# 1-Schematic_iCESDuck-ShieldControler.net
KiCad netlist of a schematic drawn in EasyEDA
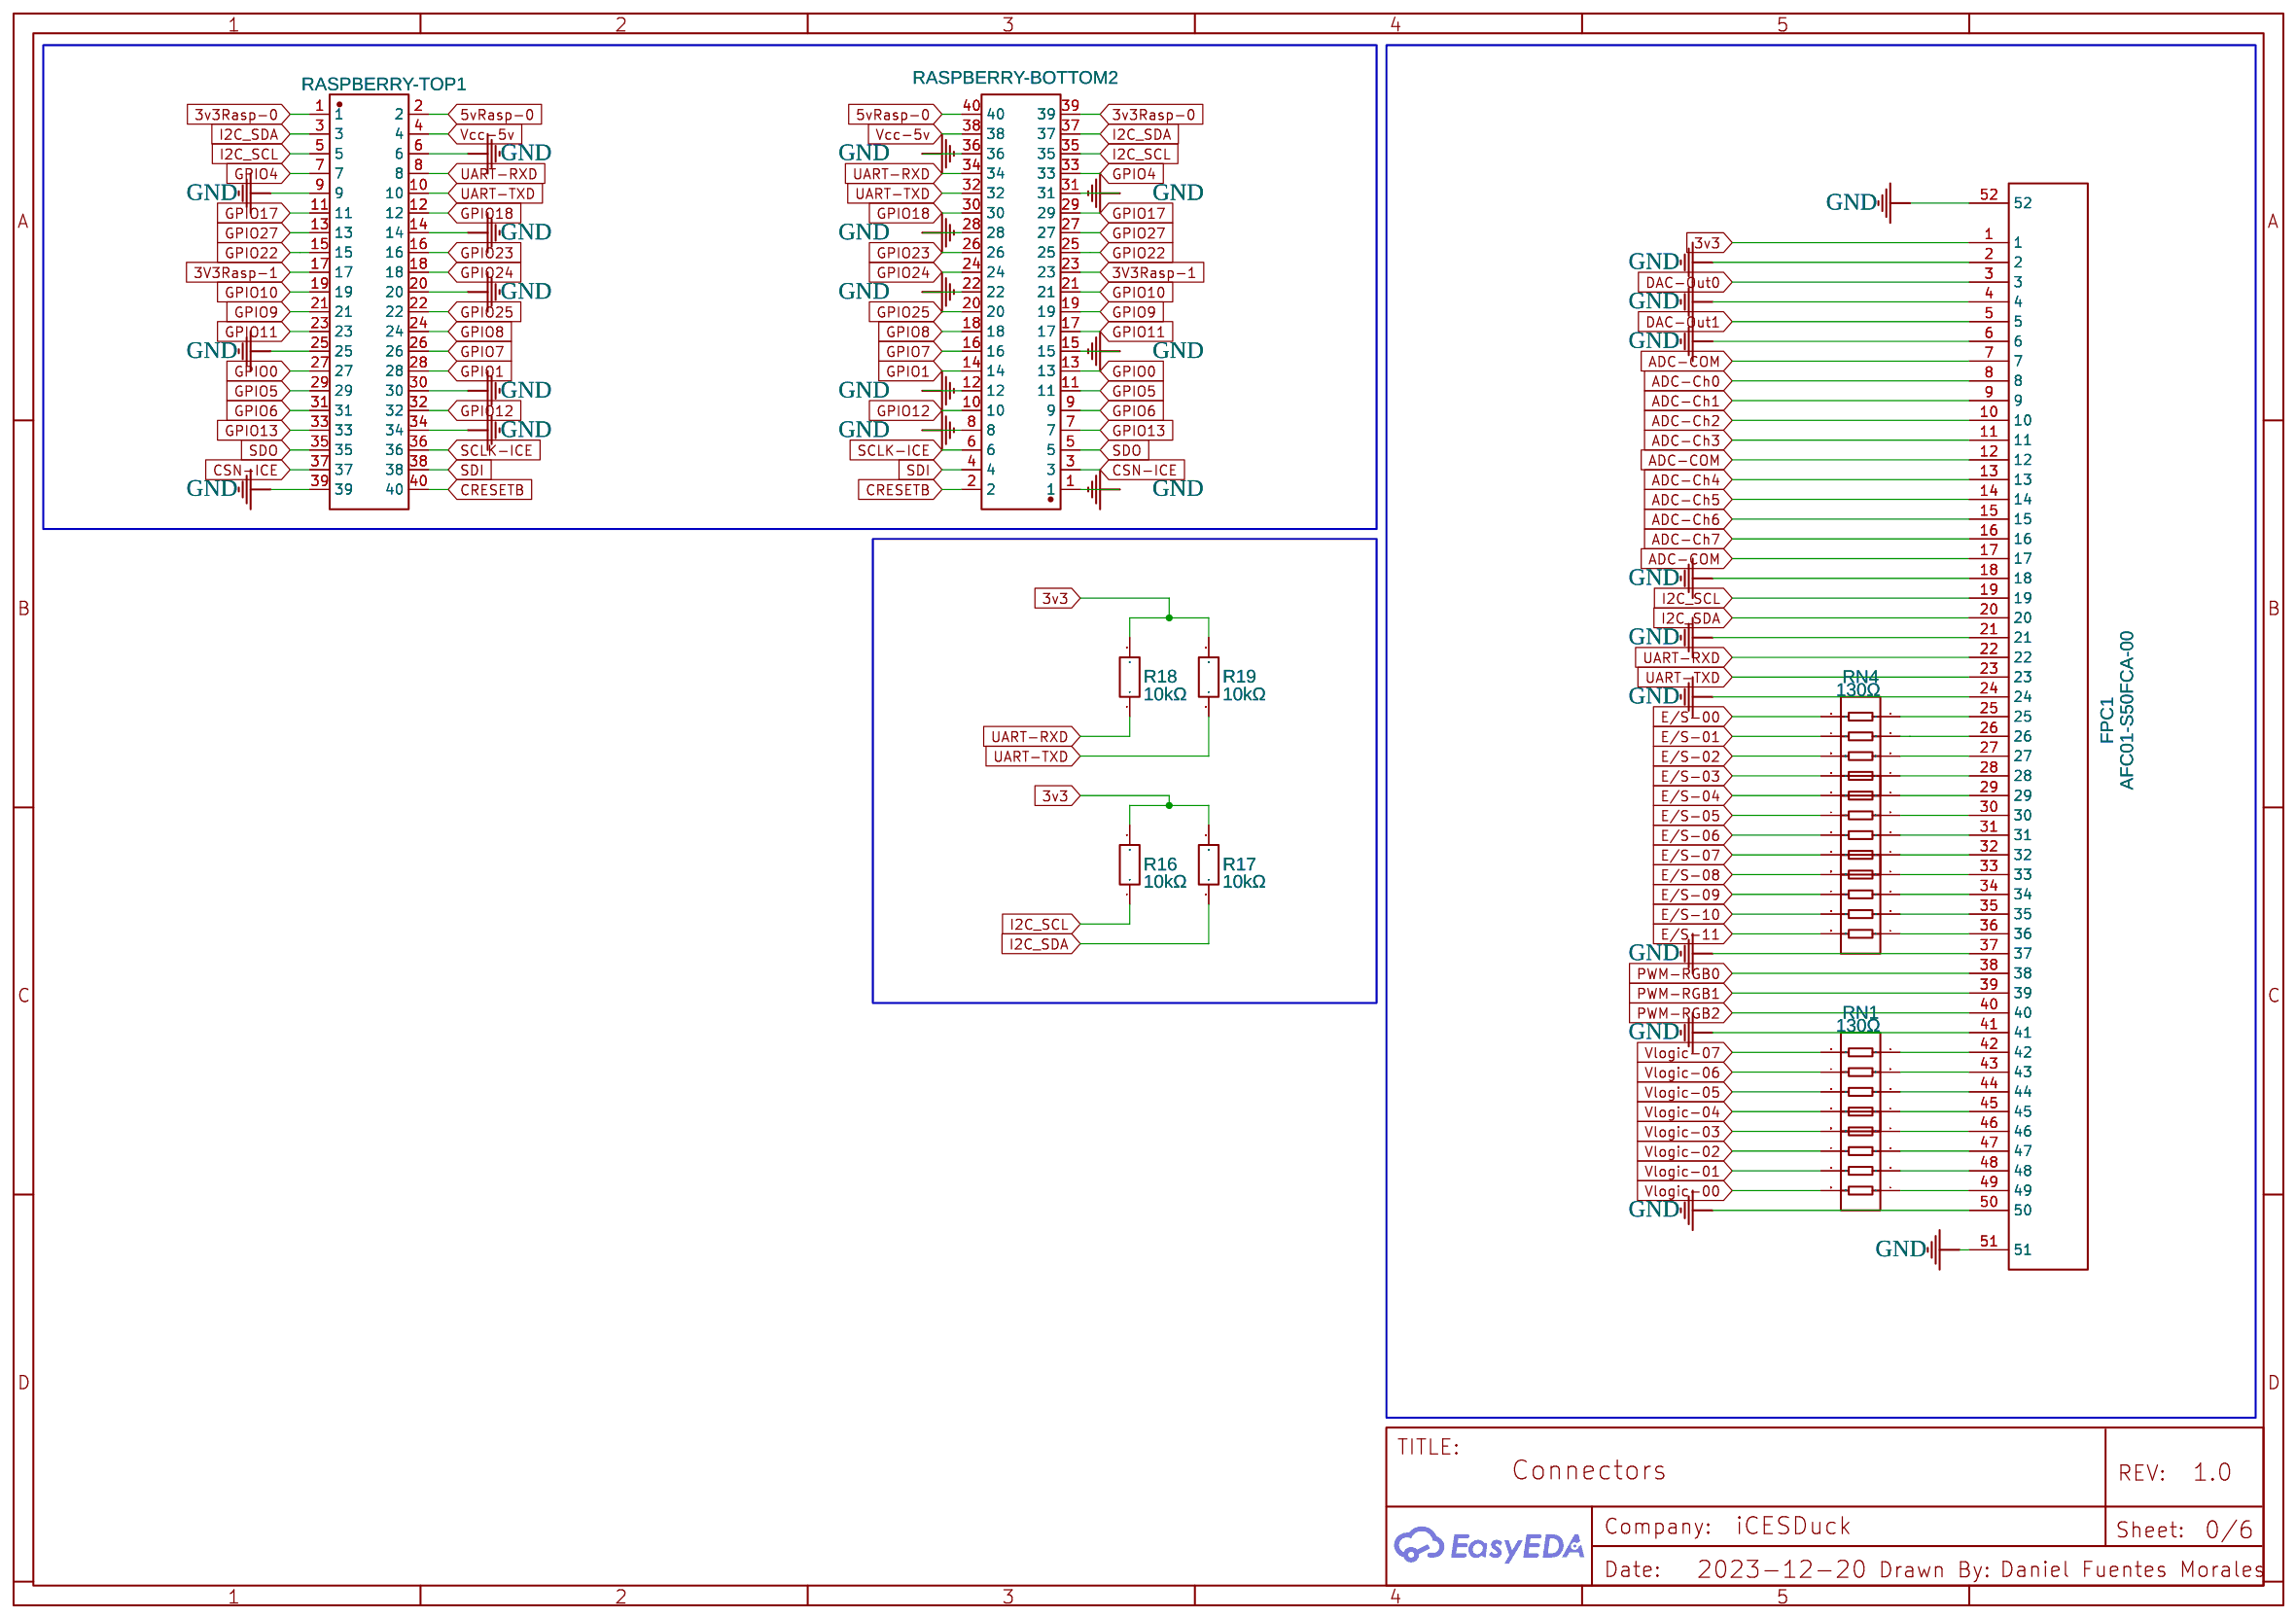
[diagram p0: Connectors]
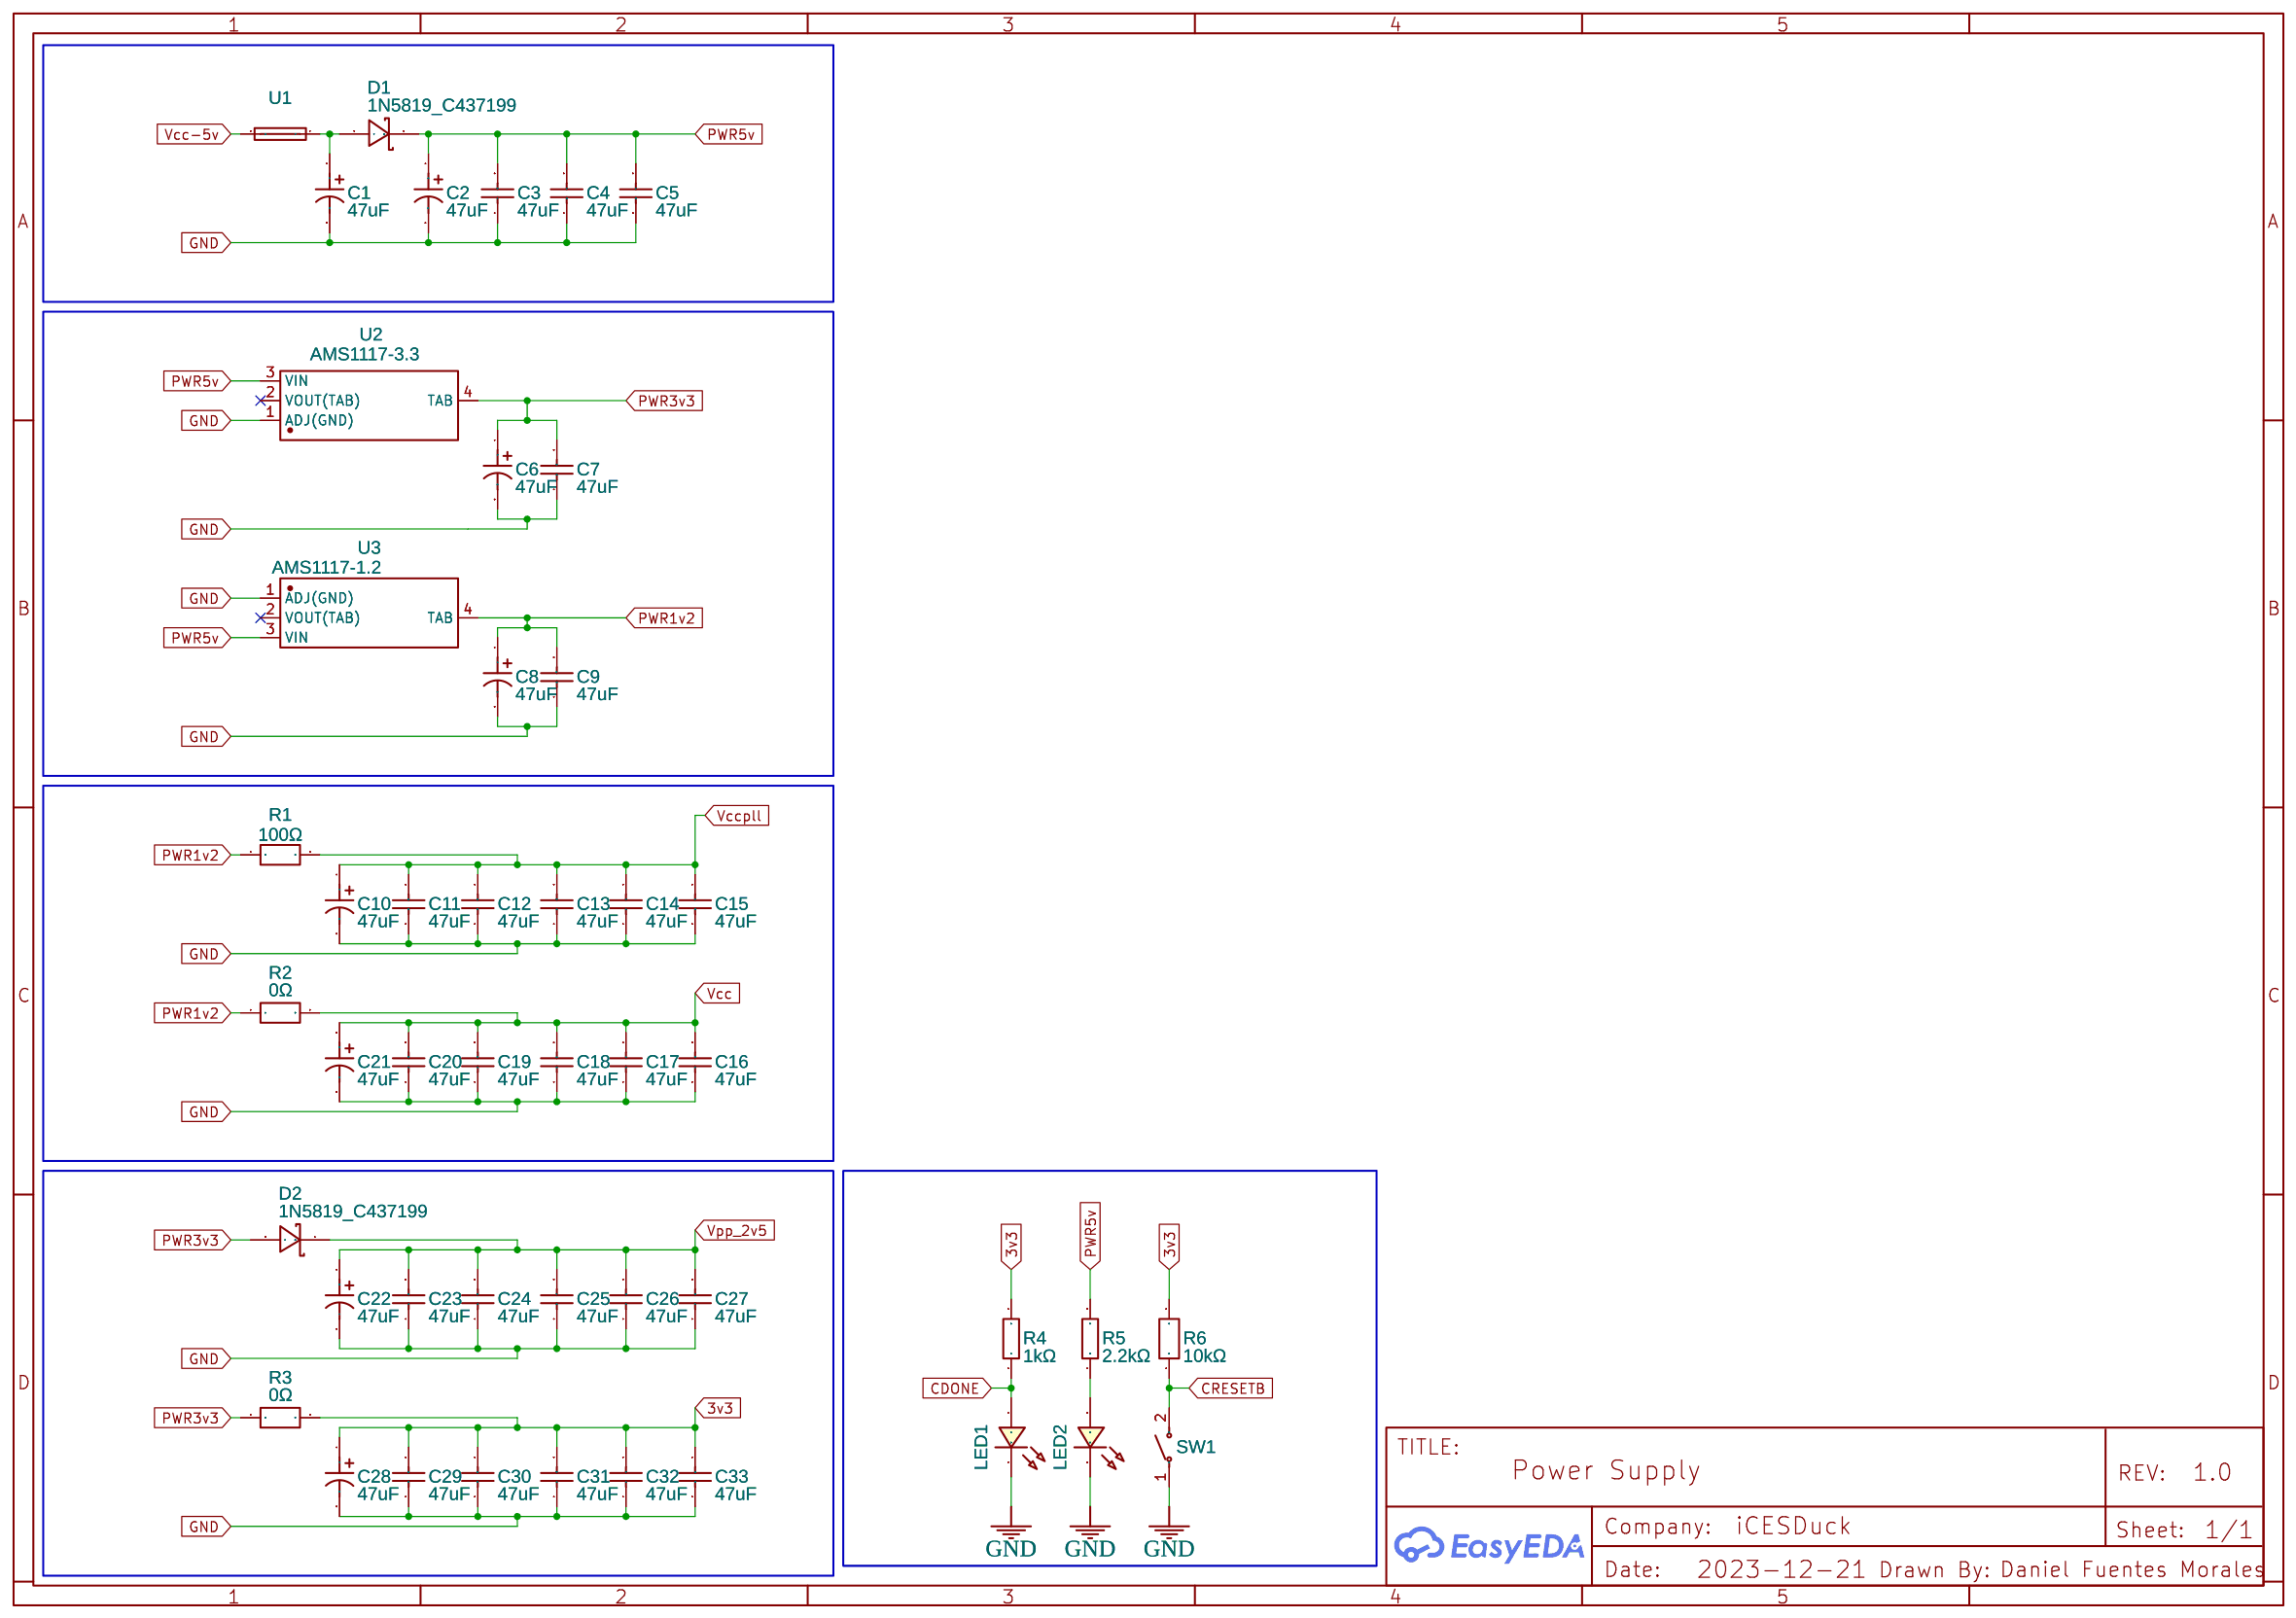
[diagram p1: power supply]
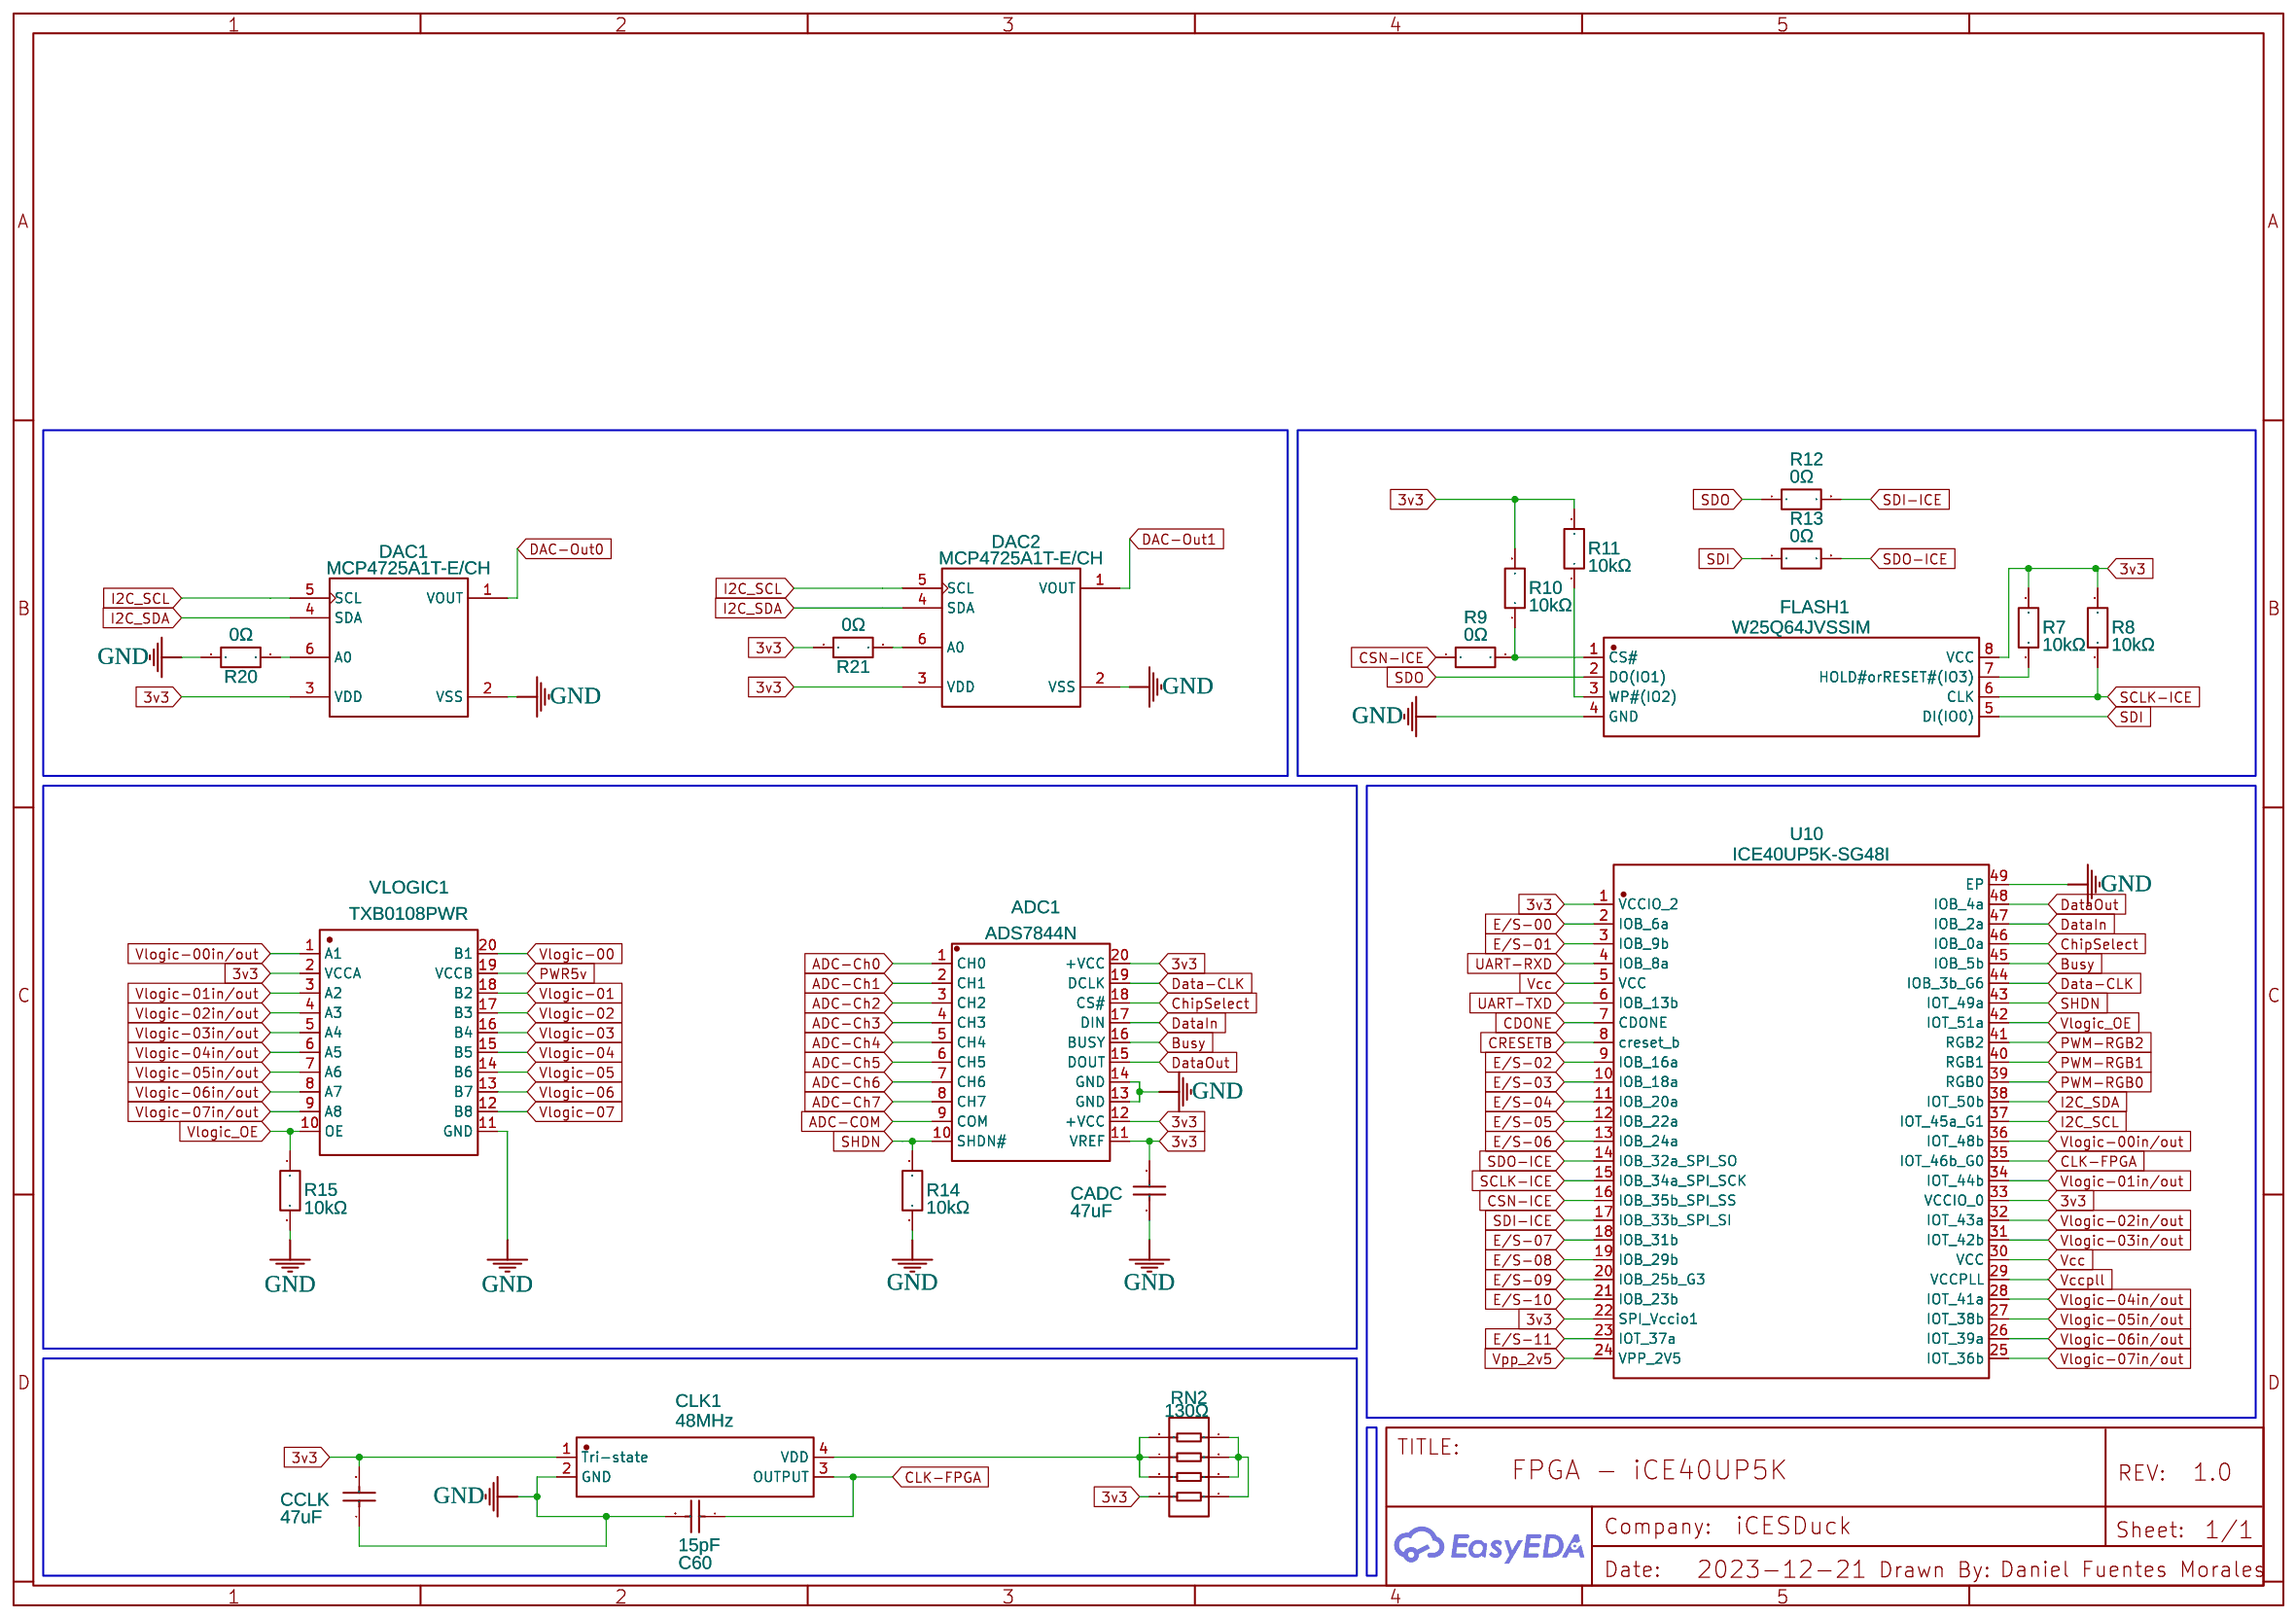
[diagram p2: FPGA - iCE40UP5k]

(export (version "E")
  (design (tool "Eeschema 10.0.6"))
  (components
    (comp (ref "FPC1")
      (value "AFC01-S50FCA-00")
      (fields (field (name "Manufacturer") "JS(钜硕电子)"))
      (libsource (lib "") (part "AFC01-S50FCA-00"))
    )
    (comp (ref "R16")
      (value "10kΩ")
      (fields (field (name "Manufacturer Part") "FRP1206J103 TS") (field (name "Manufacturer") "FOJAN(富捷)"))
      (libsource (lib "") (part "FRP1206J103 TS"))
    )
    (comp (ref "R17")
      (value "10kΩ")
      (fields (field (name "Manufacturer Part") "FRP1206J103 TS") (field (name "Manufacturer") "FOJAN(富捷)"))
      (libsource (lib "") (part "FRP1206J103 TS"))
    )
    (comp (ref "R18")
      (value "10kΩ")
      (fields (field (name "Manufacturer Part") "FRP1206J103 TS") (field (name "Manufacturer") "FOJAN(富捷)"))
      (libsource (lib "") (part "FRP1206J103 TS"))
    )
    (comp (ref "R19")
      (value "10kΩ")
      (fields (field (name "Manufacturer Part") "FRP1206J103 TS") (field (name "Manufacturer") "FOJAN(富捷)"))
      (libsource (lib "") (part "FRP1206J103 TS"))
    )
    (comp (ref "RASPBERRY-BOTTOM2")
      (value "FH-00148")
      (fields (field (name "Manufacturer") "Liansheng(连盛)"))
      (libsource (lib "") (part "FH-00148_1"))
    )
    (comp (ref "RASPBERRY-TOP1")
      (value "FH-00148")
      (fields (field (name "Manufacturer") "Liansheng(连盛)"))
      (libsource (lib "") (part "FH-00148"))
    )
    (comp (ref "RN1")
      (value "130Ω")
      (fields
        (field (name "Manufacturer Part") "4D03WGJ0131T5E")
        (field (name "Manufacturer") "UNI-ROYAL(厚声)")
      )
      (libsource (lib "") (part "4D03WGJ0131T5E"))
    )
    (comp (ref "RN3")
      (value "130Ω")
      (fields
        (field (name "Manufacturer Part") "4D03WGJ0131T5E")
        (field (name "Manufacturer") "UNI-ROYAL(厚声)")
      )
      (libsource (lib "") (part "4D03WGJ0131T5E"))
    )
    (comp (ref "RN4")
      (value "130Ω")
      (fields
        (field (name "Manufacturer Part") "4D03WGJ0131T5E")
        (field (name "Manufacturer") "UNI-ROYAL(厚声)")
      )
      (libsource (lib "") (part "4D03WGJ0131T5E"))
    )
    (comp (ref "RN5")
      (value "130Ω")
      (fields
        (field (name "Manufacturer Part") "4D03WGJ0131T5E")
        (field (name "Manufacturer") "UNI-ROYAL(厚声)")
      )
      (libsource (lib "") (part "4D03WGJ0131T5E"))
    )
    (comp (ref "RN6")
      (value "130Ω")
      (fields
        (field (name "Manufacturer Part") "4D03WGJ0131T5E")
        (field (name "Manufacturer") "UNI-ROYAL(厚声)")
      )
      (libsource (lib "") (part "4D03WGJ0131T5E"))
    )
    (comp (ref "C1")
      (value "47uF")
      (fields
        (field (name "Manufacturer Part") "CA45-A-10V-47uF-M")
        (field (name "Manufacturer") "CEC(振华新云)")
      )
      (libsource (lib "") (part "CA45-A-10V-47UF-M"))
    )
    (comp (ref "C2")
      (value "47uF")
      (fields
        (field (name "Manufacturer Part") "CA45-A-10V-47uF-M")
        (field (name "Manufacturer") "CEC(振华新云)")
      )
      (libsource (lib "") (part "CA45-A-10V-47UF-M"))
    )
    (comp (ref "C3")
      (value "47uF")
      (fields (field (name "Manufacturer Part") "C2012X5R1A476MTJ00E") (field (name "Manufacturer") "TDK"))
      (libsource (lib "") (part "C2012X5R1A476MTJ00E"))
    )
    (comp (ref "C4")
      (value "47uF")
      (fields (field (name "Manufacturer Part") "C2012X5R1A476MTJ00E") (field (name "Manufacturer") "TDK"))
      (libsource (lib "") (part "C2012X5R1A476MTJ00E"))
    )
    (comp (ref "C5")
      (value "47uF")
      (fields (field (name "Manufacturer Part") "C2012X5R1A476MTJ00E") (field (name "Manufacturer") "TDK"))
      (libsource (lib "") (part "C2012X5R1A476MTJ00E"))
    )
    (comp (ref "C6")
      (value "47uF")
      (fields
        (field (name "Manufacturer Part") "CA45-A-10V-47uF-M")
        (field (name "Manufacturer") "CEC(振华新云)")
      )
      (libsource (lib "") (part "CA45-A-10V-47UF-M"))
    )
    (comp (ref "C7")
      (value "47uF")
      (fields (field (name "Manufacturer Part") "C2012X5R1A476MTJ00E") (field (name "Manufacturer") "TDK"))
      (libsource (lib "") (part "C2012X5R1A476MTJ00E"))
    )
    (comp (ref "C8")
      (value "47uF")
      (fields
        (field (name "Manufacturer Part") "CA45-A-10V-47uF-M")
        (field (name "Manufacturer") "CEC(振华新云)")
      )
      (libsource (lib "") (part "CA45-A-10V-47UF-M"))
    )
    (comp (ref "C9")
      (value "47uF")
      (fields (field (name "Manufacturer Part") "C2012X5R1A476MTJ00E") (field (name "Manufacturer") "TDK"))
      (libsource (lib "") (part "C2012X5R1A476MTJ00E"))
    )
    (comp (ref "C10")
      (value "47uF")
      (fields
        (field (name "Manufacturer Part") "CA45-A-10V-47uF-M")
        (field (name "Manufacturer") "CEC(振华新云)")
      )
      (libsource (lib "") (part "CA45-A-10V-47UF-M"))
    )
    (comp (ref "C11")
      (value "47uF")
      (fields (field (name "Manufacturer Part") "C2012X5R1A476MTJ00E") (field (name "Manufacturer") "TDK"))
      (libsource (lib "") (part "C2012X5R1A476MTJ00E"))
    )
    (comp (ref "C12")
      (value "47uF")
      (fields (field (name "Manufacturer Part") "C2012X5R1A476MTJ00E") (field (name "Manufacturer") "TDK"))
      (libsource (lib "") (part "C2012X5R1A476MTJ00E"))
    )
    (comp (ref "C13")
      (value "47uF")
      (fields (field (name "Manufacturer Part") "C2012X5R1A476MTJ00E") (field (name "Manufacturer") "TDK"))
      (libsource (lib "") (part "C2012X5R1A476MTJ00E"))
    )
    (comp (ref "C14")
      (value "47uF")
      (fields (field (name "Manufacturer Part") "C2012X5R1A476MTJ00E") (field (name "Manufacturer") "TDK"))
      (libsource (lib "") (part "C2012X5R1A476MTJ00E"))
    )
    (comp (ref "C15")
      (value "47uF")
      (fields (field (name "Manufacturer Part") "C2012X5R1A476MTJ00E") (field (name "Manufacturer") "TDK"))
      (libsource (lib "") (part "C2012X5R1A476MTJ00E"))
    )
    (comp (ref "C16")
      (value "47uF")
      (fields (field (name "Manufacturer Part") "C2012X5R1A476MTJ00E") (field (name "Manufacturer") "TDK"))
      (libsource (lib "") (part "C2012X5R1A476MTJ00E"))
    )
    (comp (ref "C17")
      (value "47uF")
      (fields (field (name "Manufacturer Part") "C2012X5R1A476MTJ00E") (field (name "Manufacturer") "TDK"))
      (libsource (lib "") (part "C2012X5R1A476MTJ00E"))
    )
    (comp (ref "C18")
      (value "47uF")
      (fields (field (name "Manufacturer Part") "C2012X5R1A476MTJ00E") (field (name "Manufacturer") "TDK"))
      (libsource (lib "") (part "C2012X5R1A476MTJ00E"))
    )
    (comp (ref "C19")
      (value "47uF")
      (fields (field (name "Manufacturer Part") "C2012X5R1A476MTJ00E") (field (name "Manufacturer") "TDK"))
      (libsource (lib "") (part "C2012X5R1A476MTJ00E"))
    )
    (comp (ref "C20")
      (value "47uF")
      (fields (field (name "Manufacturer Part") "C2012X5R1A476MTJ00E") (field (name "Manufacturer") "TDK"))
      (libsource (lib "") (part "C2012X5R1A476MTJ00E"))
    )
    (comp (ref "C21")
      (value "47uF")
      (fields
        (field (name "Manufacturer Part") "CA45-A-10V-47uF-M")
        (field (name "Manufacturer") "CEC(振华新云)")
      )
      (libsource (lib "") (part "CA45-A-10V-47UF-M"))
    )
    (comp (ref "C22")
      (value "47uF")
      (fields
        (field (name "Manufacturer Part") "CA45-A-10V-47uF-M")
        (field (name "Manufacturer") "CEC(振华新云)")
      )
      (libsource (lib "") (part "CA45-A-10V-47UF-M"))
    )
    (comp (ref "C23")
      (value "47uF")
      (fields (field (name "Manufacturer Part") "C2012X5R1A476MTJ00E") (field (name "Manufacturer") "TDK"))
      (libsource (lib "") (part "C2012X5R1A476MTJ00E"))
    )
    (comp (ref "C24")
      (value "47uF")
      (fields (field (name "Manufacturer Part") "C2012X5R1A476MTJ00E") (field (name "Manufacturer") "TDK"))
      (libsource (lib "") (part "C2012X5R1A476MTJ00E"))
    )
    (comp (ref "C25")
      (value "47uF")
      (fields (field (name "Manufacturer Part") "C2012X5R1A476MTJ00E") (field (name "Manufacturer") "TDK"))
      (libsource (lib "") (part "C2012X5R1A476MTJ00E"))
    )
    (comp (ref "C26")
      (value "47uF")
      (fields (field (name "Manufacturer Part") "C2012X5R1A476MTJ00E") (field (name "Manufacturer") "TDK"))
      (libsource (lib "") (part "C2012X5R1A476MTJ00E"))
    )
    (comp (ref "C27")
      (value "47uF")
      (fields (field (name "Manufacturer Part") "C2012X5R1A476MTJ00E") (field (name "Manufacturer") "TDK"))
      (libsource (lib "") (part "C2012X5R1A476MTJ00E"))
    )
    (comp (ref "C28")
      (value "47uF")
      (fields
        (field (name "Manufacturer Part") "CA45-A-10V-47uF-M")
        (field (name "Manufacturer") "CEC(振华新云)")
      )
      (libsource (lib "") (part "CA45-A-10V-47UF-M"))
    )
    (comp (ref "C29")
      (value "47uF")
      (fields (field (name "Manufacturer Part") "C2012X5R1A476MTJ00E") (field (name "Manufacturer") "TDK"))
      (libsource (lib "") (part "C2012X5R1A476MTJ00E"))
    )
    (comp (ref "C30")
      (value "47uF")
      (fields (field (name "Manufacturer Part") "C2012X5R1A476MTJ00E") (field (name "Manufacturer") "TDK"))
      (libsource (lib "") (part "C2012X5R1A476MTJ00E"))
    )
    (comp (ref "C31")
      (value "47uF")
      (fields (field (name "Manufacturer Part") "C2012X5R1A476MTJ00E") (field (name "Manufacturer") "TDK"))
      (libsource (lib "") (part "C2012X5R1A476MTJ00E"))
    )
    (comp (ref "C32")
      (value "47uF")
      (fields (field (name "Manufacturer Part") "C2012X5R1A476MTJ00E") (field (name "Manufacturer") "TDK"))
      (libsource (lib "") (part "C2012X5R1A476MTJ00E"))
    )
    (comp (ref "C33")
      (value "47uF")
      (fields (field (name "Manufacturer Part") "C2012X5R1A476MTJ00E") (field (name "Manufacturer") "TDK"))
      (libsource (lib "") (part "C2012X5R1A476MTJ00E"))
    )
    (comp (ref "D1")
      (value "1N5819_C437199")
      (fields (field (name "Manufacturer Part") "1N5819") (field (name "Manufacturer") "KEXIN(科信)"))
      (libsource (lib "") (part "1N5819_C437199"))
    )
    (comp (ref "D2")
      (value "1N5819_C437199")
      (fields (field (name "Manufacturer Part") "1N5819") (field (name "Manufacturer") "KEXIN(科信)"))
      (libsource (lib "") (part "1N5819_C437199"))
    )
    (comp (ref "LED1")
      (value "LED-0603_G")
      (fields
        (field (name "Manufacturer Part") "19-217/GHC-YR1S2/3T")
        (field (name "Manufacturer") "EVERLIGHT(台湾亿光)")
      )
      (libsource (lib "") (part "LED-0603_G"))
    )
    (comp (ref "LED2")
      (value "LED-0603_G")
      (fields
        (field (name "Manufacturer Part") "19-217/GHC-YR1S2/3T")
        (field (name "Manufacturer") "EVERLIGHT(台湾亿光)")
      )
      (libsource (lib "") (part "LED-0603_G"))
    )
    (comp (ref "R1")
      (value "100Ω")
      (fields
        (field (name "Manufacturer Part") "AS05W2J0102T5E")
        (field (name "Manufacturer") "UNI-ROYAL(厚声)")
      )
      (libsource (lib "") (part "AS05W2J0102T5E"))
    )
    (comp (ref "R2")
      (value "0Ω")
      (fields
        (field (name "Manufacturer Part") "AS05W2J0102T5E")
        (field (name "Manufacturer") "UNI-ROYAL(厚声)")
      )
      (libsource (lib "") (part "AS05W2J0102T5E"))
    )
    (comp (ref "R3")
      (value "0Ω")
      (fields
        (field (name "Manufacturer Part") "AS05W2J0102T5E")
        (field (name "Manufacturer") "UNI-ROYAL(厚声)")
      )
      (libsource (lib "") (part "AS05W2J0102T5E"))
    )
    (comp (ref "R4")
      (value "1kΩ")
      (fields
        (field (name "Manufacturer Part") "0603WAF1001T5E")
        (field (name "Manufacturer") "UNI-ROYAL(厚声)")
      )
      (libsource (lib "") (part "0603WAF1001T5E"))
    )
    (comp (ref "R5")
      (value "2.2kΩ")
      (fields
        (field (name "Manufacturer Part") "0603WAF2201T5E")
        (field (name "Manufacturer") "UNI-ROYAL(厚声)")
      )
      (libsource (lib "") (part "0603WAF2201T5E"))
    )
    (comp (ref "R6")
      (value "10kΩ")
      (fields (field (name "Manufacturer Part") "FRP1206J103 TS") (field (name "Manufacturer") "FOJAN(富捷)"))
      (libsource (lib "") (part "FRP1206J103 TS"))
    )
    (comp (ref "SW1")
      (value "TS-1088R-02026")
      (fields (field (name "Manufacturer") "XUNPU(讯普)"))
      (libsource (lib "") (part "TS-1088R-02026"))
    )
    (comp (ref "U1")
      (value "0494001.NR")
      (fields (field (name "Manufacturer") "Littelfuse(美国力特)"))
      (libsource (lib "") (part "0494001.NR"))
    )
    (comp (ref "U2")
      (value "AMS1117-3.3")
      (fields (field (name "Manufacturer") "UMW(广东友台半导体)"))
      (libsource (lib "") (part "AMS1117-3.3_C347222"))
    )
    (comp (ref "U3")
      (value "AMS1117-1.2")
      (fields (field (name "Manufacturer") "UMW(广东友台半导体)"))
      (libsource (lib "") (part "AMS1117-1.2_C347218"))
    )
    (comp (ref "ADC1")
      (value "ADS7844N")
      (fields (field (name "Manufacturer") "TI(德州仪器)"))
      (libsource (lib "") (part "ADS7844N"))
    )
    (comp (ref "C60")
      (value "15pF")
      (fields
        (field (name "Manufacturer Part") "CL10C150JB8NNNC")
        (field (name "Manufacturer") "SAMSUNG(三星)")
      )
      (libsource (lib "") (part "CL10C150JB8NNNC"))
    )
    (comp (ref "CADC")
      (value "47uF")
      (fields (field (name "Manufacturer Part") "C2012X5R1A476MTJ00E") (field (name "Manufacturer") "TDK"))
      (libsource (lib "") (part "C2012X5R1A476MTJ00E_1"))
    )
    (comp (ref "CCLK")
      (value "47uF")
      (fields (field (name "Manufacturer Part") "C2012X5R1A476MTJ00E") (field (name "Manufacturer") "TDK"))
      (libsource (lib "") (part "C2012X5R1A476MTJ00E"))
    )
    (comp (ref "CLK1")
      (value "48MHz")
      (fields
        (field (name "Manufacturer Part") "S3D48.000000B20F30T")
        (field (name "Manufacturer") "SCTF(星通时频)")
      )
      (libsource (lib "") (part "S3D48.000000B20F30T"))
    )
    (comp (ref "DAC1")
      (value "MCP4725A1T-E/CH")
      (fields (field (name "Manufacturer") "MICROCHIP(美国微芯)"))
      (libsource (lib "") (part "MCP4725A1T-E/CH"))
    )
    (comp (ref "DAC2")
      (value "MCP4725A1T-E/CH")
      (fields (field (name "Manufacturer") "MICROCHIP(美国微芯)"))
      (libsource (lib "") (part "MCP4725A1T-E/CH"))
    )
    (comp (ref "FLASH1")
      (value "W25Q64JVSSIM")
      (fields (field (name "Manufacturer") "WINBOND(华邦)"))
      (libsource (lib "") (part "W25Q64JVSSIM"))
    )
    (comp (ref "R7")
      (value "10kΩ")
      (fields (field (name "Manufacturer Part") "FRP1206J103 TS") (field (name "Manufacturer") "FOJAN(富捷)"))
      (libsource (lib "") (part "FRP1206J103 TS"))
    )
    (comp (ref "R8")
      (value "10kΩ")
      (fields (field (name "Manufacturer Part") "FRP1206J103 TS") (field (name "Manufacturer") "FOJAN(富捷)"))
      (libsource (lib "") (part "FRP1206J103 TS"))
    )
    (comp (ref "R9")
      (value "0Ω")
      (fields
        (field (name "Manufacturer Part") "AS05W2J0102T5E")
        (field (name "Manufacturer") "UNI-ROYAL(厚声)")
      )
      (libsource (lib "") (part "AS05W2J0102T5E"))
    )
    (comp (ref "R10")
      (value "10kΩ")
      (fields (field (name "Manufacturer Part") "FRP1206J103 TS") (field (name "Manufacturer") "FOJAN(富捷)"))
      (libsource (lib "") (part "FRP1206J103 TS"))
    )
    (comp (ref "R11")
      (value "10kΩ")
      (fields (field (name "Manufacturer Part") "FRP1206J103 TS") (field (name "Manufacturer") "FOJAN(富捷)"))
      (libsource (lib "") (part "FRP1206J103 TS"))
    )
    (comp (ref "R12")
      (value "0Ω")
      (fields
        (field (name "Manufacturer Part") "AS05W2J0102T5E")
        (field (name "Manufacturer") "UNI-ROYAL(厚声)")
      )
      (libsource (lib "") (part "AS05W2J0102T5E"))
    )
    (comp (ref "R13")
      (value "0Ω")
      (fields
        (field (name "Manufacturer Part") "AS05W2J0102T5E")
        (field (name "Manufacturer") "UNI-ROYAL(厚声)")
      )
      (libsource (lib "") (part "AS05W2J0102T5E"))
    )
    (comp (ref "R14")
      (value "10kΩ")
      (fields (field (name "Manufacturer Part") "FRP1206J103 TS") (field (name "Manufacturer") "FOJAN(富捷)"))
      (libsource (lib "") (part "FRP1206J103 TS"))
    )
    (comp (ref "R15")
      (value "10kΩ")
      (fields (field (name "Manufacturer Part") "FRP1206J103 TS") (field (name "Manufacturer") "FOJAN(富捷)"))
      (libsource (lib "") (part "FRP1206J103 TS_1"))
    )
    (comp (ref "R20")
      (value "0Ω")
      (fields
        (field (name "Manufacturer Part") "AS05W2J0102T5E")
        (field (name "Manufacturer") "UNI-ROYAL(厚声)")
      )
      (libsource (lib "") (part "AS05W2J0102T5E"))
    )
    (comp (ref "R21")
      (value "0Ω")
      (fields
        (field (name "Manufacturer Part") "AS05W2J0102T5E")
        (field (name "Manufacturer") "UNI-ROYAL(厚声)")
      )
      (libsource (lib "") (part "AS05W2J0102T5E"))
    )
    (comp (ref "RN2")
      (value "130Ω")
      (fields
        (field (name "Manufacturer Part") "4D03WGJ0131T5E")
        (field (name "Manufacturer") "UNI-ROYAL(厚声)")
      )
      (libsource (lib "") (part "4D03WGJ0131T5E"))
    )
    (comp (ref "U10")
      (value "ICE40UP5K-SG48I")
      (fields (field (name "Manufacturer") "LATTICE(莱迪思)"))
      (libsource (lib "") (part "ICE40UP5K-SG48I"))
    )
    (comp (ref "VLOGIC1")
      (value "TXB0108PWR")
      (fields (field (name "Manufacturer") "TI(德州仪器)"))
      (libsource (lib "") (part "TXB0108PWR"))
    )
  )
  (nets
    (net (code "1") (name "3V3Rasp-1") (class "Default")
      (node (ref "RASPBERRY-BOTTOM2") (pin "23") (pinfunction "23_23") (pintype "unspecified"))
      (node (ref "RASPBERRY-TOP1") (pin "17") (pinfunction "17_17") (pintype "unspecified"))
    )
    (net (code "2") (name "3v3") (class "Default")
      (node (ref "ADC1") (pin "11") (pinfunction "VREF_11") (pintype "unspecified"))
      (node (ref "ADC1") (pin "12") (pinfunction "+VCC_12") (pintype "unspecified"))
      (node (ref "ADC1") (pin "20") (pinfunction "+VCC_20") (pintype "unspecified"))
      (node (ref "C28") (pin "1") (pinfunction "1_1") (pintype "input"))
      (node (ref "C29") (pin "2") (pinfunction "2_2") (pintype "input"))
      (node (ref "C30") (pin "2") (pinfunction "2_2") (pintype "input"))
      (node (ref "C31") (pin "2") (pinfunction "2_2") (pintype "input"))
      (node (ref "C32") (pin "2") (pinfunction "2_2") (pintype "input"))
      (node (ref "C33") (pin "2") (pinfunction "2_2") (pintype "input"))
      (node (ref "CADC") (pin "2") (pinfunction "2_2") (pintype "input"))
      (node (ref "CCLK") (pin "2") (pinfunction "2_2") (pintype "input"))
      (node (ref "CLK1") (pin "1") (pinfunction "Tri-state_1") (pintype "unspecified"))
      (node (ref "DAC1") (pin "3") (pinfunction "VDD_3") (pintype "passive"))
      (node (ref "DAC2") (pin "3") (pinfunction "VDD_3") (pintype "passive"))
      (node (ref "FLASH1") (pin "8") (pinfunction "VCC_8") (pintype "unspecified"))
      (node (ref "FPC1") (pin "1") (pinfunction "1_1") (pintype "unspecified"))
      (node (ref "R10") (pin "2") (pinfunction "2_2") (pintype "unspecified"))
      (node (ref "R11") (pin "2") (pinfunction "2_2") (pintype "unspecified"))
      (node (ref "R16") (pin "2") (pinfunction "2_2") (pintype "unspecified"))
      (node (ref "R17") (pin "2") (pinfunction "2_2") (pintype "unspecified"))
      (node (ref "R18") (pin "2") (pinfunction "2_2") (pintype "unspecified"))
      (node (ref "R19") (pin "2") (pinfunction "2_2") (pintype "unspecified"))
      (node (ref "R21") (pin "1") (pinfunction "1_1") (pintype "unspecified"))
      (node (ref "R3") (pin "2") (pinfunction "2_2") (pintype "unspecified"))
      (node (ref "R4") (pin "2") (pinfunction "2_2") (pintype "input"))
      (node (ref "R6") (pin "2") (pinfunction "2_2") (pintype "unspecified"))
      (node (ref "R7") (pin "2") (pinfunction "2_2") (pintype "unspecified"))
      (node (ref "R8") (pin "2") (pinfunction "2_2") (pintype "unspecified"))
      (node (ref "RN2") (pin "5") (pinfunction "5_5") (pintype "unspecified"))
      (node (ref "U10") (pin "1") (pinfunction "VCCIO_2_1") (pintype "unspecified"))
      (node (ref "U10") (pin "22") (pinfunction "SPI_Vccio1_22") (pintype "unspecified"))
      (node (ref "U10") (pin "33") (pinfunction "VCCIO_0_33") (pintype "unspecified"))
      (node (ref "VLOGIC1") (pin "2") (pinfunction "VCCA_2") (pintype "unspecified"))
    )
    (net (code "3") (name "3v3Rasp-0") (class "Default")
      (node (ref "RASPBERRY-BOTTOM2") (pin "39") (pinfunction "39_39") (pintype "unspecified"))
      (node (ref "RASPBERRY-TOP1") (pin "1") (pinfunction "1_1") (pintype "unspecified"))
    )
    (net (code "4") (name "5vRasp-0") (class "Default")
      (node (ref "RASPBERRY-BOTTOM2") (pin "40") (pinfunction "40_40") (pintype "unspecified"))
      (node (ref "RASPBERRY-TOP1") (pin "2") (pinfunction "2_2") (pintype "unspecified"))
    )
    (net (code "5") (name "ADC-COM") (class "Default")
      (node (ref "ADC1") (pin "9") (pinfunction "COM_9") (pintype "unspecified"))
      (node (ref "FPC1") (pin "12") (pinfunction "12_12") (pintype "unspecified"))
      (node (ref "FPC1") (pin "17") (pinfunction "17_17") (pintype "unspecified"))
      (node (ref "FPC1") (pin "7") (pinfunction "7_7") (pintype "unspecified"))
    )
    (net (code "6") (name "ADC-Ch0") (class "Default")
      (node (ref "ADC1") (pin "1") (pinfunction "CH0_1") (pintype "unspecified"))
      (node (ref "FPC1") (pin "8") (pinfunction "8_8") (pintype "unspecified"))
    )
    (net (code "7") (name "ADC-Ch1") (class "Default")
      (node (ref "ADC1") (pin "2") (pinfunction "CH1_2") (pintype "unspecified"))
      (node (ref "FPC1") (pin "9") (pinfunction "9_9") (pintype "unspecified"))
    )
    (net (code "8") (name "ADC-Ch2") (class "Default")
      (node (ref "ADC1") (pin "3") (pinfunction "CH2_3") (pintype "unspecified"))
      (node (ref "FPC1") (pin "10") (pinfunction "10_10") (pintype "unspecified"))
    )
    (net (code "9") (name "ADC-Ch3") (class "Default")
      (node (ref "ADC1") (pin "4") (pinfunction "CH3_4") (pintype "unspecified"))
      (node (ref "FPC1") (pin "11") (pinfunction "11_11") (pintype "unspecified"))
    )
    (net (code "10") (name "ADC-Ch4") (class "Default")
      (node (ref "ADC1") (pin "5") (pinfunction "CH4_5") (pintype "unspecified"))
      (node (ref "FPC1") (pin "13") (pinfunction "13_13") (pintype "unspecified"))
    )
    (net (code "11") (name "ADC-Ch5") (class "Default")
      (node (ref "ADC1") (pin "6") (pinfunction "CH5_6") (pintype "unspecified"))
      (node (ref "FPC1") (pin "14") (pinfunction "14_14") (pintype "unspecified"))
    )
    (net (code "12") (name "ADC-Ch6") (class "Default")
      (node (ref "ADC1") (pin "7") (pinfunction "CH6_7") (pintype "unspecified"))
      (node (ref "FPC1") (pin "15") (pinfunction "15_15") (pintype "unspecified"))
    )
    (net (code "13") (name "ADC-Ch7") (class "Default")
      (node (ref "ADC1") (pin "8") (pinfunction "CH7_8") (pintype "unspecified"))
      (node (ref "FPC1") (pin "16") (pinfunction "16_16") (pintype "unspecified"))
    )
    (net (code "14") (name "Busy") (class "Default")
      (node (ref "ADC1") (pin "16") (pinfunction "BUSY_16") (pintype "unspecified"))
      (node (ref "U10") (pin "45") (pinfunction "IOB_5b_45") (pintype "unspecified"))
    )
    (net (code "15") (name "CDONE") (class "Default")
      (node (ref "LED1") (pin "1") (pinfunction "1_1") (pintype "unspecified"))
      (node (ref "R4") (pin "1") (pinfunction "1_1") (pintype "input"))
      (node (ref "U10") (pin "7") (pinfunction "CDONE_7") (pintype "unspecified"))
    )
    (net (code "16") (name "CLK-FPGA") (class "Default")
      (node (ref "C60") (pin "1") (pinfunction "1_1") (pintype "input"))
      (node (ref "CLK1") (pin "3") (pinfunction "OUTPUT_3") (pintype "unspecified"))
      (node (ref "U10") (pin "35") (pinfunction "IOT_46b_G0_35") (pintype "unspecified"))
    )
    (net (code "17") (name "CRESETB") (class "Default")
      (node (ref "R6") (pin "1") (pinfunction "1_1") (pintype "unspecified"))
      (node (ref "RASPBERRY-BOTTOM2") (pin "2") (pinfunction "2_2") (pintype "unspecified"))
      (node (ref "RASPBERRY-TOP1") (pin "40") (pinfunction "40_40") (pintype "unspecified"))
      (node (ref "SW1") (pin "2") (pinfunction "2_2") (pintype "unspecified"))
      (node (ref "U10") (pin "8") (pinfunction "creset_b_8") (pintype "unspecified"))
    )
    (net (code "18") (name "CSN-ICE") (class "Default")
      (node (ref "R9") (pin "1") (pinfunction "1_1") (pintype "unspecified"))
      (node (ref "RASPBERRY-BOTTOM2") (pin "3") (pinfunction "3_3") (pintype "unspecified"))
      (node (ref "RASPBERRY-TOP1") (pin "37") (pinfunction "37_37") (pintype "unspecified"))
      (node (ref "U10") (pin "16") (pinfunction "IOB_35b_SPI_SS_16") (pintype "unspecified"))
    )
    (net (code "19") (name "ChipSelect") (class "Default")
      (node (ref "ADC1") (pin "18") (pinfunction "CS#_18") (pintype "unspecified"))
      (node (ref "U10") (pin "46") (pinfunction "IOB_0a_46") (pintype "unspecified"))
    )
    (net (code "20") (name "DAC-Out0") (class "Default")
      (node (ref "DAC1") (pin "1") (pinfunction "VOUT_1") (pintype "output"))
      (node (ref "FPC1") (pin "3") (pinfunction "3_3") (pintype "unspecified"))
    )
    (net (code "21") (name "DAC-Out1") (class "Default")
      (node (ref "DAC2") (pin "1") (pinfunction "VOUT_1") (pintype "output"))
      (node (ref "FPC1") (pin "5") (pinfunction "5_5") (pintype "unspecified"))
    )
    (net (code "22") (name "Data-CLK") (class "Default")
      (node (ref "ADC1") (pin "19") (pinfunction "DCLK_19") (pintype "unspecified"))
      (node (ref "U10") (pin "44") (pinfunction "IOB_3b_G6_44") (pintype "unspecified"))
    )
    (net (code "23") (name "DataIn") (class "Default")
      (node (ref "ADC1") (pin "17") (pinfunction "DIN_17") (pintype "unspecified"))
      (node (ref "U10") (pin "47") (pinfunction "IOB_2a_47") (pintype "unspecified"))
    )
    (net (code "24") (name "DataOut") (class "Default")
      (node (ref "ADC1") (pin "15") (pinfunction "DOUT_15") (pintype "unspecified"))
      (node (ref "U10") (pin "48") (pinfunction "IOB_4a_48") (pintype "unspecified"))
    )
    (net (code "25") (name "E{slash}S-00") (class "Default")
      (node (ref "RN4") (pin "8") (pinfunction "8_8") (pintype "unspecified"))
      (node (ref "U10") (pin "2") (pinfunction "IOB_6a_2") (pintype "unspecified"))
    )
    (net (code "26") (name "E{slash}S-01") (class "Default")
      (node (ref "RN4") (pin "7") (pinfunction "7_7") (pintype "unspecified"))
      (node (ref "U10") (pin "3") (pinfunction "IOB_9b_3") (pintype "unspecified"))
    )
    (net (code "27") (name "E{slash}S-02") (class "Default")
      (node (ref "RN4") (pin "6") (pinfunction "6_6") (pintype "unspecified"))
      (node (ref "U10") (pin "9") (pinfunction "IOB_16a_9") (pintype "unspecified"))
    )
    (net (code "28") (name "E{slash}S-03") (class "Default")
      (node (ref "RN4") (pin "5") (pinfunction "5_5") (pintype "unspecified"))
      (node (ref "U10") (pin "10") (pinfunction "IOB_18a_10") (pintype "unspecified"))
    )
    (net (code "29") (name "E{slash}S-04") (class "Default")
      (node (ref "RN5") (pin "8") (pinfunction "8_8") (pintype "unspecified"))
      (node (ref "U10") (pin "11") (pinfunction "IOB_20a_11") (pintype "unspecified"))
    )
    (net (code "30") (name "E{slash}S-05") (class "Default")
      (node (ref "RN5") (pin "7") (pinfunction "7_7") (pintype "unspecified"))
      (node (ref "U10") (pin "12") (pinfunction "IOB_22a_12") (pintype "unspecified"))
    )
    (net (code "31") (name "E{slash}S-06") (class "Default")
      (node (ref "RN5") (pin "6") (pinfunction "6_6") (pintype "unspecified"))
      (node (ref "U10") (pin "13") (pinfunction "IOB_24a_13") (pintype "unspecified"))
    )
    (net (code "32") (name "E{slash}S-07") (class "Default")
      (node (ref "RN5") (pin "5") (pinfunction "5_5") (pintype "unspecified"))
      (node (ref "U10") (pin "18") (pinfunction "IOB_31b_18") (pintype "unspecified"))
    )
    (net (code "33") (name "E{slash}S-08") (class "Default")
      (node (ref "RN6") (pin "8") (pinfunction "8_8") (pintype "unspecified"))
      (node (ref "U10") (pin "19") (pinfunction "IOB_29b_19") (pintype "unspecified"))
    )
    (net (code "34") (name "E{slash}S-09") (class "Default")
      (node (ref "RN6") (pin "7") (pinfunction "7_7") (pintype "unspecified"))
      (node (ref "U10") (pin "20") (pinfunction "IOB_25b_G3_20") (pintype "unspecified"))
    )
    (net (code "35") (name "E{slash}S-10") (class "Default")
      (node (ref "RN6") (pin "6") (pinfunction "6_6") (pintype "unspecified"))
      (node (ref "U10") (pin "21") (pinfunction "IOB_23b_21") (pintype "unspecified"))
    )
    (net (code "36") (name "E{slash}S-11") (class "Default")
      (node (ref "RN6") (pin "5") (pinfunction "5_5") (pintype "unspecified"))
      (node (ref "U10") (pin "23") (pinfunction "IOT_37a_23") (pintype "unspecified"))
    )
    (net (code "37") (name "GND") (class "Default")
      (node (ref "ADC1") (pin "13") (pinfunction "GND_13") (pintype "unspecified"))
      (node (ref "ADC1") (pin "14") (pinfunction "GND_14") (pintype "unspecified"))
      (node (ref "C1") (pin "2") (pinfunction "2_2") (pintype "input"))
      (node (ref "C10") (pin "2") (pinfunction "2_2") (pintype "input"))
      (node (ref "C11") (pin "1") (pinfunction "1_1") (pintype "input"))
      (node (ref "C12") (pin "1") (pinfunction "1_1") (pintype "input"))
      (node (ref "C13") (pin "1") (pinfunction "1_1") (pintype "input"))
      (node (ref "C14") (pin "1") (pinfunction "1_1") (pintype "input"))
      (node (ref "C15") (pin "1") (pinfunction "1_1") (pintype "input"))
      (node (ref "C16") (pin "1") (pinfunction "1_1") (pintype "input"))
      (node (ref "C17") (pin "1") (pinfunction "1_1") (pintype "input"))
      (node (ref "C18") (pin "1") (pinfunction "1_1") (pintype "input"))
      (node (ref "C19") (pin "1") (pinfunction "1_1") (pintype "input"))
      (node (ref "C2") (pin "2") (pinfunction "2_2") (pintype "input"))
      (node (ref "C20") (pin "1") (pinfunction "1_1") (pintype "input"))
      (node (ref "C21") (pin "2") (pinfunction "2_2") (pintype "input"))
      (node (ref "C22") (pin "2") (pinfunction "2_2") (pintype "input"))
      (node (ref "C23") (pin "1") (pinfunction "1_1") (pintype "input"))
      (node (ref "C24") (pin "1") (pinfunction "1_1") (pintype "input"))
      (node (ref "C25") (pin "1") (pinfunction "1_1") (pintype "input"))
      (node (ref "C26") (pin "1") (pinfunction "1_1") (pintype "input"))
      (node (ref "C27") (pin "1") (pinfunction "1_1") (pintype "input"))
      (node (ref "C28") (pin "2") (pinfunction "2_2") (pintype "input"))
      (node (ref "C29") (pin "1") (pinfunction "1_1") (pintype "input"))
      (node (ref "C3") (pin "1") (pinfunction "1_1") (pintype "input"))
      (node (ref "C30") (pin "1") (pinfunction "1_1") (pintype "input"))
      (node (ref "C31") (pin "1") (pinfunction "1_1") (pintype "input"))
      (node (ref "C32") (pin "1") (pinfunction "1_1") (pintype "input"))
      (node (ref "C33") (pin "1") (pinfunction "1_1") (pintype "input"))
      (node (ref "C4") (pin "1") (pinfunction "1_1") (pintype "input"))
      (node (ref "C5") (pin "1") (pinfunction "1_1") (pintype "input"))
      (node (ref "C6") (pin "2") (pinfunction "2_2") (pintype "input"))
      (node (ref "C60") (pin "2") (pinfunction "2_2") (pintype "input"))
      (node (ref "C7") (pin "1") (pinfunction "1_1") (pintype "input"))
      (node (ref "C8") (pin "2") (pinfunction "2_2") (pintype "input"))
      (node (ref "C9") (pin "1") (pinfunction "1_1") (pintype "input"))
      (node (ref "CADC") (pin "1") (pinfunction "1_1") (pintype "input"))
      (node (ref "CCLK") (pin "1") (pinfunction "1_1") (pintype "input"))
      (node (ref "CLK1") (pin "2") (pinfunction "GND_2") (pintype "unspecified"))
      (node (ref "DAC1") (pin "2") (pinfunction "VSS_2") (pintype "passive"))
      (node (ref "DAC2") (pin "2") (pinfunction "VSS_2") (pintype "passive"))
      (node (ref "FLASH1") (pin "4") (pinfunction "GND_4") (pintype "unspecified"))
      (node (ref "FPC1") (pin "18") (pinfunction "18_18") (pintype "unspecified"))
      (node (ref "FPC1") (pin "2") (pinfunction "2_2") (pintype "unspecified"))
      (node (ref "FPC1") (pin "21") (pinfunction "21_21") (pintype "unspecified"))
      (node (ref "FPC1") (pin "24") (pinfunction "24_24") (pintype "unspecified"))
      (node (ref "FPC1") (pin "37") (pinfunction "37_37") (pintype "unspecified"))
      (node (ref "FPC1") (pin "4") (pinfunction "4_4") (pintype "unspecified"))
      (node (ref "FPC1") (pin "41") (pinfunction "41_41") (pintype "unspecified"))
      (node (ref "FPC1") (pin "50") (pinfunction "50_50") (pintype "unspecified"))
      (node (ref "FPC1") (pin "51") (pinfunction "51_51") (pintype "unspecified"))
      (node (ref "FPC1") (pin "52") (pinfunction "52_52") (pintype "unspecified"))
      (node (ref "FPC1") (pin "6") (pinfunction "6_6") (pintype "unspecified"))
      (node (ref "LED1") (pin "2") (pinfunction "2_2") (pintype "unspecified"))
      (node (ref "LED2") (pin "2") (pinfunction "2_2") (pintype "unspecified"))
      (node (ref "R14") (pin "1") (pinfunction "1_1") (pintype "unspecified"))
      (node (ref "R15") (pin "2") (pinfunction "2_2") (pintype "unspecified"))
      (node (ref "R20") (pin "1") (pinfunction "1_1") (pintype "unspecified"))
      (node (ref "RASPBERRY-BOTTOM2") (pin "1") (pinfunction "1_1") (pintype "unspecified"))
      (node (ref "RASPBERRY-BOTTOM2") (pin "12") (pinfunction "12_12") (pintype "unspecified"))
      (node (ref "RASPBERRY-BOTTOM2") (pin "15") (pinfunction "15_15") (pintype "unspecified"))
      (node (ref "RASPBERRY-BOTTOM2") (pin "22") (pinfunction "22_22") (pintype "unspecified"))
      (node (ref "RASPBERRY-BOTTOM2") (pin "28") (pinfunction "28_28") (pintype "unspecified"))
      (node (ref "RASPBERRY-BOTTOM2") (pin "31") (pinfunction "31_31") (pintype "unspecified"))
      (node (ref "RASPBERRY-BOTTOM2") (pin "36") (pinfunction "36_36") (pintype "unspecified"))
      (node (ref "RASPBERRY-BOTTOM2") (pin "8") (pinfunction "8_8") (pintype "unspecified"))
      (node (ref "RASPBERRY-TOP1") (pin "14") (pinfunction "14_14") (pintype "unspecified"))
      (node (ref "RASPBERRY-TOP1") (pin "20") (pinfunction "20_20") (pintype "unspecified"))
      (node (ref "RASPBERRY-TOP1") (pin "25") (pinfunction "25_25") (pintype "unspecified"))
      (node (ref "RASPBERRY-TOP1") (pin "30") (pinfunction "30_30") (pintype "unspecified"))
      (node (ref "RASPBERRY-TOP1") (pin "34") (pinfunction "34_34") (pintype "unspecified"))
      (node (ref "RASPBERRY-TOP1") (pin "39") (pinfunction "39_39") (pintype "unspecified"))
      (node (ref "RASPBERRY-TOP1") (pin "6") (pinfunction "6_6") (pintype "unspecified"))
      (node (ref "RASPBERRY-TOP1") (pin "9") (pinfunction "9_9") (pintype "unspecified"))
      (node (ref "SW1") (pin "1") (pinfunction "1_1") (pintype "unspecified"))
      (node (ref "U10") (pin "49") (pinfunction "EP_49") (pintype "unspecified"))
      (node (ref "U2") (pin "1") (pinfunction "ADJ(GND)_1") (pintype "unspecified"))
      (node (ref "U3") (pin "1") (pinfunction "ADJ(GND)_1") (pintype "unspecified"))
      (node (ref "VLOGIC1") (pin "11") (pinfunction "GND_11") (pintype "unspecified"))
    )
    (net (code "38") (name "GPIO0") (class "Default")
      (node (ref "RASPBERRY-BOTTOM2") (pin "13") (pinfunction "13_13") (pintype "unspecified"))
      (node (ref "RASPBERRY-TOP1") (pin "27") (pinfunction "27_27") (pintype "unspecified"))
    )
    (net (code "39") (name "GPIO1") (class "Default")
      (node (ref "RASPBERRY-BOTTOM2") (pin "14") (pinfunction "14_14") (pintype "unspecified"))
      (node (ref "RASPBERRY-TOP1") (pin "28") (pinfunction "28_28") (pintype "unspecified"))
    )
    (net (code "40") (name "GPIO4") (class "Default")
      (node (ref "RASPBERRY-BOTTOM2") (pin "33") (pinfunction "33_33") (pintype "unspecified"))
      (node (ref "RASPBERRY-TOP1") (pin "7") (pinfunction "7_7") (pintype "unspecified"))
    )
    (net (code "41") (name "GPIO5") (class "Default")
      (node (ref "RASPBERRY-BOTTOM2") (pin "11") (pinfunction "11_11") (pintype "unspecified"))
      (node (ref "RASPBERRY-TOP1") (pin "29") (pinfunction "29_29") (pintype "unspecified"))
    )
    (net (code "42") (name "GPIO6") (class "Default")
      (node (ref "RASPBERRY-BOTTOM2") (pin "9") (pinfunction "9_9") (pintype "unspecified"))
      (node (ref "RASPBERRY-TOP1") (pin "31") (pinfunction "31_31") (pintype "unspecified"))
    )
    (net (code "43") (name "GPIO7") (class "Default")
      (node (ref "RASPBERRY-BOTTOM2") (pin "16") (pinfunction "16_16") (pintype "unspecified"))
      (node (ref "RASPBERRY-TOP1") (pin "26") (pinfunction "26_26") (pintype "unspecified"))
    )
    (net (code "44") (name "GPIO8") (class "Default")
      (node (ref "RASPBERRY-BOTTOM2") (pin "18") (pinfunction "18_18") (pintype "unspecified"))
      (node (ref "RASPBERRY-TOP1") (pin "24") (pinfunction "24_24") (pintype "unspecified"))
    )
    (net (code "45") (name "GPIO9") (class "Default")
      (node (ref "RASPBERRY-BOTTOM2") (pin "19") (pinfunction "19_19") (pintype "unspecified"))
      (node (ref "RASPBERRY-TOP1") (pin "21") (pinfunction "21_21") (pintype "unspecified"))
    )
    (net (code "46") (name "GPIO10") (class "Default")
      (node (ref "RASPBERRY-BOTTOM2") (pin "21") (pinfunction "21_21") (pintype "unspecified"))
      (node (ref "RASPBERRY-TOP1") (pin "19") (pinfunction "19_19") (pintype "unspecified"))
    )
    (net (code "47") (name "GPIO11") (class "Default")
      (node (ref "RASPBERRY-BOTTOM2") (pin "17") (pinfunction "17_17") (pintype "unspecified"))
      (node (ref "RASPBERRY-TOP1") (pin "23") (pinfunction "23_23") (pintype "unspecified"))
    )
    (net (code "48") (name "GPIO12") (class "Default")
      (node (ref "RASPBERRY-BOTTOM2") (pin "10") (pinfunction "10_10") (pintype "unspecified"))
      (node (ref "RASPBERRY-TOP1") (pin "32") (pinfunction "32_32") (pintype "unspecified"))
    )
    (net (code "49") (name "GPIO13") (class "Default")
      (node (ref "RASPBERRY-BOTTOM2") (pin "7") (pinfunction "7_7") (pintype "unspecified"))
      (node (ref "RASPBERRY-TOP1") (pin "33") (pinfunction "33_33") (pintype "unspecified"))
    )
    (net (code "50") (name "GPIO17") (class "Default")
      (node (ref "RASPBERRY-BOTTOM2") (pin "29") (pinfunction "29_29") (pintype "unspecified"))
      (node (ref "RASPBERRY-TOP1") (pin "11") (pinfunction "11_11") (pintype "unspecified"))
    )
    (net (code "51") (name "GPIO18") (class "Default")
      (node (ref "RASPBERRY-BOTTOM2") (pin "30") (pinfunction "30_30") (pintype "unspecified"))
      (node (ref "RASPBERRY-TOP1") (pin "12") (pinfunction "12_12") (pintype "unspecified"))
    )
    (net (code "52") (name "GPIO22") (class "Default")
      (node (ref "RASPBERRY-BOTTOM2") (pin "25") (pinfunction "25_25") (pintype "unspecified"))
      (node (ref "RASPBERRY-TOP1") (pin "15") (pinfunction "15_15") (pintype "unspecified"))
    )
    (net (code "53") (name "GPIO23") (class "Default")
      (node (ref "RASPBERRY-BOTTOM2") (pin "26") (pinfunction "26_26") (pintype "unspecified"))
      (node (ref "RASPBERRY-TOP1") (pin "16") (pinfunction "16_16") (pintype "unspecified"))
    )
    (net (code "54") (name "GPIO24") (class "Default")
      (node (ref "RASPBERRY-BOTTOM2") (pin "24") (pinfunction "24_24") (pintype "unspecified"))
      (node (ref "RASPBERRY-TOP1") (pin "18") (pinfunction "18_18") (pintype "unspecified"))
    )
    (net (code "55") (name "GPIO25") (class "Default")
      (node (ref "RASPBERRY-BOTTOM2") (pin "20") (pinfunction "20_20") (pintype "unspecified"))
      (node (ref "RASPBERRY-TOP1") (pin "22") (pinfunction "22_22") (pintype "unspecified"))
    )
    (net (code "56") (name "GPIO27") (class "Default")
      (node (ref "RASPBERRY-BOTTOM2") (pin "27") (pinfunction "27_27") (pintype "unspecified"))
      (node (ref "RASPBERRY-TOP1") (pin "13") (pinfunction "13_13") (pintype "unspecified"))
    )
    (net (code "57") (name "I2C_SCL") (class "Default")
      (node (ref "DAC1") (pin "5") (pinfunction "SCL_5") (pintype "unspecified"))
      (node (ref "DAC2") (pin "5") (pinfunction "SCL_5") (pintype "unspecified"))
      (node (ref "FPC1") (pin "19") (pinfunction "19_19") (pintype "unspecified"))
      (node (ref "R16") (pin "1") (pinfunction "1_1") (pintype "unspecified"))
      (node (ref "RASPBERRY-BOTTOM2") (pin "35") (pinfunction "35_35") (pintype "unspecified"))
      (node (ref "RASPBERRY-TOP1") (pin "5") (pinfunction "5_5") (pintype "unspecified"))
      (node (ref "U10") (pin "37") (pinfunction "IOT_45a_G1_37") (pintype "unspecified"))
    )
    (net (code "58") (name "I2C_SDA") (class "Default")
      (node (ref "DAC1") (pin "4") (pinfunction "SDA_4") (pintype "bidirectional"))
      (node (ref "DAC2") (pin "4") (pinfunction "SDA_4") (pintype "bidirectional"))
      (node (ref "FPC1") (pin "20") (pinfunction "20_20") (pintype "unspecified"))
      (node (ref "R17") (pin "1") (pinfunction "1_1") (pintype "unspecified"))
      (node (ref "RASPBERRY-BOTTOM2") (pin "37") (pinfunction "37_37") (pintype "unspecified"))
      (node (ref "RASPBERRY-TOP1") (pin "3") (pinfunction "3_3") (pintype "unspecified"))
      (node (ref "U10") (pin "38") (pinfunction "IOT_50b_38") (pintype "unspecified"))
    )
    (net (code "59") (name "Net-(CLK1-VDD)") (class "Default")
      (node (ref "CLK1") (pin "4") (pinfunction "VDD_4") (pintype "unspecified"))
      (node (ref "RN2") (pin "6") (pinfunction "6_6") (pintype "unspecified"))
      (node (ref "RN2") (pin "7") (pinfunction "7_7") (pintype "unspecified"))
      (node (ref "RN2") (pin "8") (pinfunction "8_8") (pintype "unspecified"))
    )
    (net (code "60") (name "Net-(D1-A)") (class "Default")
      (node (ref "C1") (pin "1") (pinfunction "1_1") (pintype "input"))
      (node (ref "D1") (pin "2") (pinfunction "A_2") (pintype "unspecified"))
      (node (ref "U1") (pin "1") (pinfunction "1_1") (pintype "unspecified"))
    )
    (net (code "61") (name "Net-(DAC1-A0)") (class "Default")
      (node (ref "DAC1") (pin "6") (pinfunction "A0_6") (pintype "unspecified"))
      (node (ref "R20") (pin "2") (pinfunction "2_2") (pintype "unspecified"))
    )
    (net (code "62") (name "Net-(DAC2-A0)") (class "Default")
      (node (ref "DAC2") (pin "6") (pinfunction "A0_6") (pintype "unspecified"))
      (node (ref "R21") (pin "2") (pinfunction "2_2") (pintype "unspecified"))
    )
    (net (code "63") (name "Net-(FLASH1-CS#)") (class "Default")
      (node (ref "FLASH1") (pin "1") (pinfunction "CS#_1") (pintype "unspecified"))
      (node (ref "R10") (pin "1") (pinfunction "1_1") (pintype "unspecified"))
      (node (ref "R9") (pin "2") (pinfunction "2_2") (pintype "unspecified"))
    )
    (net (code "64") (name "Net-(FLASH1-HOLD#orRESET#(IO3))") (class "Default")
      (node (ref "FLASH1") (pin "7") (pinfunction "HOLD#orRESET#(IO3)_7") (pintype "unspecified"))
      (node (ref "R7") (pin "1") (pinfunction "1_1") (pintype "unspecified"))
    )
    (net (code "65") (name "Net-(FLASH1-WP#(IO2))") (class "Default")
      (node (ref "FLASH1") (pin "3") (pinfunction "WP#(IO2)_3") (pintype "unspecified"))
      (node (ref "R11") (pin "1") (pinfunction "1_1") (pintype "unspecified"))
    )
    (net (code "66") (name "Net-(FPC1-Pad25)") (class "Default")
      (node (ref "FPC1") (pin "25") (pinfunction "25_25") (pintype "unspecified"))
      (node (ref "RN4") (pin "1") (pinfunction "1_1") (pintype "unspecified"))
    )
    (net (code "67") (name "Net-(FPC1-Pad26)") (class "Default")
      (node (ref "FPC1") (pin "26") (pinfunction "26_26") (pintype "unspecified"))
      (node (ref "RN4") (pin "2") (pinfunction "2_2") (pintype "unspecified"))
    )
    (net (code "68") (name "Net-(FPC1-Pad27)") (class "Default")
      (node (ref "FPC1") (pin "27") (pinfunction "27_27") (pintype "unspecified"))
      (node (ref "RN4") (pin "3") (pinfunction "3_3") (pintype "unspecified"))
    )
    (net (code "69") (name "Net-(FPC1-Pad28)") (class "Default")
      (node (ref "FPC1") (pin "28") (pinfunction "28_28") (pintype "unspecified"))
      (node (ref "RN4") (pin "4") (pinfunction "4_4") (pintype "unspecified"))
    )
    (net (code "70") (name "Net-(FPC1-Pad29)") (class "Default")
      (node (ref "FPC1") (pin "29") (pinfunction "29_29") (pintype "unspecified"))
      (node (ref "RN5") (pin "1") (pinfunction "1_1") (pintype "unspecified"))
    )
    (net (code "71") (name "Net-(FPC1-Pad30)") (class "Default")
      (node (ref "FPC1") (pin "30") (pinfunction "30_30") (pintype "unspecified"))
      (node (ref "RN5") (pin "2") (pinfunction "2_2") (pintype "unspecified"))
    )
    (net (code "72") (name "Net-(FPC1-Pad31)") (class "Default")
      (node (ref "FPC1") (pin "31") (pinfunction "31_31") (pintype "unspecified"))
      (node (ref "RN5") (pin "3") (pinfunction "3_3") (pintype "unspecified"))
    )
    (net (code "73") (name "Net-(FPC1-Pad32)") (class "Default")
      (node (ref "FPC1") (pin "32") (pinfunction "32_32") (pintype "unspecified"))
      (node (ref "RN5") (pin "4") (pinfunction "4_4") (pintype "unspecified"))
    )
    (net (code "74") (name "Net-(FPC1-Pad33)") (class "Default")
      (node (ref "FPC1") (pin "33") (pinfunction "33_33") (pintype "unspecified"))
      (node (ref "RN6") (pin "1") (pinfunction "1_1") (pintype "unspecified"))
    )
    (net (code "75") (name "Net-(FPC1-Pad34)") (class "Default")
      (node (ref "FPC1") (pin "34") (pinfunction "34_34") (pintype "unspecified"))
      (node (ref "RN6") (pin "2") (pinfunction "2_2") (pintype "unspecified"))
    )
    (net (code "76") (name "Net-(FPC1-Pad35)") (class "Default")
      (node (ref "FPC1") (pin "35") (pinfunction "35_35") (pintype "unspecified"))
      (node (ref "RN6") (pin "3") (pinfunction "3_3") (pintype "unspecified"))
    )
    (net (code "77") (name "Net-(FPC1-Pad36)") (class "Default")
      (node (ref "FPC1") (pin "36") (pinfunction "36_36") (pintype "unspecified"))
      (node (ref "RN6") (pin "4") (pinfunction "4_4") (pintype "unspecified"))
    )
    (net (code "78") (name "Net-(FPC1-Pad42)") (class "Default")
      (node (ref "FPC1") (pin "42") (pinfunction "42_42") (pintype "unspecified"))
      (node (ref "RN1") (pin "1") (pinfunction "1_1") (pintype "unspecified"))
    )
    (net (code "79") (name "Net-(FPC1-Pad43)") (class "Default")
      (node (ref "FPC1") (pin "43") (pinfunction "43_43") (pintype "unspecified"))
      (node (ref "RN1") (pin "2") (pinfunction "2_2") (pintype "unspecified"))
    )
    (net (code "80") (name "Net-(FPC1-Pad44)") (class "Default")
      (node (ref "FPC1") (pin "44") (pinfunction "44_44") (pintype "unspecified"))
      (node (ref "RN1") (pin "3") (pinfunction "3_3") (pintype "unspecified"))
    )
    (net (code "81") (name "Net-(FPC1-Pad45)") (class "Default")
      (node (ref "FPC1") (pin "45") (pinfunction "45_45") (pintype "unspecified"))
      (node (ref "RN1") (pin "4") (pinfunction "4_4") (pintype "unspecified"))
    )
    (net (code "82") (name "Net-(FPC1-Pad46)") (class "Default")
      (node (ref "FPC1") (pin "46") (pinfunction "46_46") (pintype "unspecified"))
      (node (ref "RN3") (pin "1") (pinfunction "1_1") (pintype "unspecified"))
    )
    (net (code "83") (name "Net-(FPC1-Pad47)") (class "Default")
      (node (ref "FPC1") (pin "47") (pinfunction "47_47") (pintype "unspecified"))
      (node (ref "RN3") (pin "2") (pinfunction "2_2") (pintype "unspecified"))
    )
    (net (code "84") (name "Net-(FPC1-Pad48)") (class "Default")
      (node (ref "FPC1") (pin "48") (pinfunction "48_48") (pintype "unspecified"))
      (node (ref "RN3") (pin "3") (pinfunction "3_3") (pintype "unspecified"))
    )
    (net (code "85") (name "Net-(FPC1-Pad49)") (class "Default")
      (node (ref "FPC1") (pin "49") (pinfunction "49_49") (pintype "unspecified"))
      (node (ref "RN3") (pin "4") (pinfunction "4_4") (pintype "unspecified"))
    )
    (net (code "86") (name "Net-(LED2-Pad1)") (class "Default")
      (node (ref "LED2") (pin "1") (pinfunction "1_1") (pintype "unspecified"))
      (node (ref "R5") (pin "1") (pinfunction "1_1") (pintype "input"))
    )
    (net (code "87") (name "Net-(RN2-Pad1)") (class "Default")
      (node (ref "RN2") (pin "1") (pinfunction "1_1") (pintype "unspecified"))
      (node (ref "RN2") (pin "2") (pinfunction "2_2") (pintype "unspecified"))
      (node (ref "RN2") (pin "3") (pinfunction "3_3") (pintype "unspecified"))
      (node (ref "RN2") (pin "4") (pinfunction "4_4") (pintype "unspecified"))
    )
    (net (code "88") (name "PWM-RGB0") (class "Default")
      (node (ref "FPC1") (pin "38") (pinfunction "38_38") (pintype "unspecified"))
      (node (ref "U10") (pin "39") (pinfunction "RGB0_39") (pintype "unspecified"))
    )
    (net (code "89") (name "PWM-RGB1") (class "Default")
      (node (ref "FPC1") (pin "39") (pinfunction "39_39") (pintype "unspecified"))
      (node (ref "U10") (pin "40") (pinfunction "RGB1_40") (pintype "unspecified"))
    )
    (net (code "90") (name "PWM-RGB2") (class "Default")
      (node (ref "FPC1") (pin "40") (pinfunction "40_40") (pintype "unspecified"))
      (node (ref "U10") (pin "41") (pinfunction "RGB2_41") (pintype "unspecified"))
    )
    (net (code "91") (name "PWR1v2") (class "Default")
      (node (ref "C8") (pin "1") (pinfunction "1_1") (pintype "input"))
      (node (ref "C9") (pin "2") (pinfunction "2_2") (pintype "input"))
      (node (ref "R1") (pin "1") (pinfunction "1_1") (pintype "unspecified"))
      (node (ref "R2") (pin "1") (pinfunction "1_1") (pintype "unspecified"))
      (node (ref "U3") (pin "4") (pinfunction "TAB_4") (pintype "unspecified"))
    )
    (net (code "92") (name "PWR3v3") (class "Default")
      (node (ref "C6") (pin "1") (pinfunction "1_1") (pintype "input"))
      (node (ref "C7") (pin "2") (pinfunction "2_2") (pintype "input"))
      (node (ref "D2") (pin "2") (pinfunction "A_2") (pintype "unspecified"))
      (node (ref "R3") (pin "1") (pinfunction "1_1") (pintype "unspecified"))
      (node (ref "U2") (pin "4") (pinfunction "TAB_4") (pintype "unspecified"))
    )
    (net (code "93") (name "PWR5v") (class "Default")
      (node (ref "C2") (pin "1") (pinfunction "1_1") (pintype "input"))
      (node (ref "C3") (pin "2") (pinfunction "2_2") (pintype "input"))
      (node (ref "C4") (pin "2") (pinfunction "2_2") (pintype "input"))
      (node (ref "C5") (pin "2") (pinfunction "2_2") (pintype "input"))
      (node (ref "D1") (pin "1") (pinfunction "C_1") (pintype "unspecified"))
      (node (ref "R5") (pin "2") (pinfunction "2_2") (pintype "input"))
      (node (ref "U2") (pin "3") (pinfunction "VIN_3") (pintype "unspecified"))
      (node (ref "U3") (pin "3") (pinfunction "VIN_3") (pintype "unspecified"))
      (node (ref "VLOGIC1") (pin "19") (pinfunction "VCCB_19") (pintype "unspecified"))
    )
    (net (code "94") (name "SCLK-ICE") (class "Default")
      (node (ref "FLASH1") (pin "6") (pinfunction "CLK_6") (pintype "unspecified"))
      (node (ref "R8") (pin "1") (pinfunction "1_1") (pintype "unspecified"))
      (node (ref "RASPBERRY-BOTTOM2") (pin "6") (pinfunction "6_6") (pintype "unspecified"))
      (node (ref "RASPBERRY-TOP1") (pin "36") (pinfunction "36_36") (pintype "unspecified"))
      (node (ref "U10") (pin "15") (pinfunction "IOB_34a_SPI_SCK_15") (pintype "unspecified"))
    )
    (net (code "95") (name "SDI") (class "Default")
      (node (ref "FLASH1") (pin "5") (pinfunction "DI(IO0)_5") (pintype "unspecified"))
      (node (ref "R13") (pin "1") (pinfunction "1_1") (pintype "unspecified"))
      (node (ref "RASPBERRY-BOTTOM2") (pin "4") (pinfunction "4_4") (pintype "unspecified"))
      (node (ref "RASPBERRY-TOP1") (pin "38") (pinfunction "38_38") (pintype "unspecified"))
    )
    (net (code "96") (name "SDI-ICE") (class "Default")
      (node (ref "R12") (pin "2") (pinfunction "2_2") (pintype "unspecified"))
      (node (ref "U10") (pin "17") (pinfunction "IOB_33b_SPI_SI_17") (pintype "unspecified"))
    )
    (net (code "97") (name "SDO") (class "Default")
      (node (ref "FLASH1") (pin "2") (pinfunction "DO(IO1)_2") (pintype "unspecified"))
      (node (ref "R12") (pin "1") (pinfunction "1_1") (pintype "unspecified"))
      (node (ref "RASPBERRY-BOTTOM2") (pin "5") (pinfunction "5_5") (pintype "unspecified"))
      (node (ref "RASPBERRY-TOP1") (pin "35") (pinfunction "35_35") (pintype "unspecified"))
    )
    (net (code "98") (name "SDO-ICE") (class "Default")
      (node (ref "R13") (pin "2") (pinfunction "2_2") (pintype "unspecified"))
      (node (ref "U10") (pin "14") (pinfunction "IOB_32a_SPI_SO_14") (pintype "unspecified"))
    )
    (net (code "99") (name "SHDN") (class "Default")
      (node (ref "ADC1") (pin "10") (pinfunction "SHDN#_10") (pintype "unspecified"))
      (node (ref "R14") (pin "2") (pinfunction "2_2") (pintype "unspecified"))
      (node (ref "U10") (pin "43") (pinfunction "IOT_49a_43") (pintype "unspecified"))
    )
    (net (code "100") (name "UART-RXD") (class "Default")
      (node (ref "FPC1") (pin "22") (pinfunction "22_22") (pintype "unspecified"))
      (node (ref "R18") (pin "1") (pinfunction "1_1") (pintype "unspecified"))
      (node (ref "RASPBERRY-BOTTOM2") (pin "34") (pinfunction "34_34") (pintype "unspecified"))
      (node (ref "RASPBERRY-TOP1") (pin "8") (pinfunction "8_8") (pintype "unspecified"))
      (node (ref "U10") (pin "4") (pinfunction "IOB_8a_4") (pintype "unspecified"))
    )
    (net (code "101") (name "UART-TXD") (class "Default")
      (node (ref "FPC1") (pin "23") (pinfunction "23_23") (pintype "unspecified"))
      (node (ref "R19") (pin "1") (pinfunction "1_1") (pintype "unspecified"))
      (node (ref "RASPBERRY-BOTTOM2") (pin "32") (pinfunction "32_32") (pintype "unspecified"))
      (node (ref "RASPBERRY-TOP1") (pin "10") (pinfunction "10_10") (pintype "unspecified"))
      (node (ref "U10") (pin "6") (pinfunction "IOB_13b_6") (pintype "unspecified"))
    )
    (net (code "102") (name "Vcc") (class "Default")
      (node (ref "C16") (pin "2") (pinfunction "2_2") (pintype "input"))
      (node (ref "C17") (pin "2") (pinfunction "2_2") (pintype "input"))
      (node (ref "C18") (pin "2") (pinfunction "2_2") (pintype "input"))
      (node (ref "C19") (pin "2") (pinfunction "2_2") (pintype "input"))
      (node (ref "C20") (pin "2") (pinfunction "2_2") (pintype "input"))
      (node (ref "C21") (pin "1") (pinfunction "1_1") (pintype "input"))
      (node (ref "R2") (pin "2") (pinfunction "2_2") (pintype "unspecified"))
      (node (ref "U10") (pin "30") (pinfunction "VCC_30") (pintype "unspecified"))
      (node (ref "U10") (pin "5") (pinfunction "VCC_5") (pintype "unspecified"))
    )
    (net (code "103") (name "Vcc-5v") (class "Default")
      (node (ref "RASPBERRY-BOTTOM2") (pin "38") (pinfunction "38_38") (pintype "unspecified"))
      (node (ref "RASPBERRY-TOP1") (pin "4") (pinfunction "4_4") (pintype "unspecified"))
      (node (ref "U1") (pin "2") (pinfunction "2_2") (pintype "unspecified"))
    )
    (net (code "104") (name "Vccpll") (class "Default")
      (node (ref "C10") (pin "1") (pinfunction "1_1") (pintype "input"))
      (node (ref "C11") (pin "2") (pinfunction "2_2") (pintype "input"))
      (node (ref "C12") (pin "2") (pinfunction "2_2") (pintype "input"))
      (node (ref "C13") (pin "2") (pinfunction "2_2") (pintype "input"))
      (node (ref "C14") (pin "2") (pinfunction "2_2") (pintype "input"))
      (node (ref "C15") (pin "2") (pinfunction "2_2") (pintype "input"))
      (node (ref "R1") (pin "2") (pinfunction "2_2") (pintype "unspecified"))
      (node (ref "U10") (pin "29") (pinfunction "VCCPLL_29") (pintype "unspecified"))
    )
    (net (code "105") (name "Vlogic-00") (class "Default")
      (node (ref "RN3") (pin "5") (pinfunction "5_5") (pintype "unspecified"))
      (node (ref "VLOGIC1") (pin "20") (pinfunction "B1_20") (pintype "unspecified"))
    )
    (net (code "106") (name "Vlogic-00in{slash}out") (class "Default")
      (node (ref "U10") (pin "36") (pinfunction "IOT_48b_36") (pintype "unspecified"))
      (node (ref "VLOGIC1") (pin "1") (pinfunction "A1_1") (pintype "unspecified"))
    )
    (net (code "107") (name "Vlogic-01") (class "Default")
      (node (ref "RN3") (pin "6") (pinfunction "6_6") (pintype "unspecified"))
      (node (ref "VLOGIC1") (pin "18") (pinfunction "B2_18") (pintype "unspecified"))
    )
    (net (code "108") (name "Vlogic-01in{slash}out") (class "Default")
      (node (ref "U10") (pin "34") (pinfunction "IOT_44b_34") (pintype "unspecified"))
      (node (ref "VLOGIC1") (pin "3") (pinfunction "A2_3") (pintype "unspecified"))
    )
    (net (code "109") (name "Vlogic-02") (class "Default")
      (node (ref "RN3") (pin "7") (pinfunction "7_7") (pintype "unspecified"))
      (node (ref "VLOGIC1") (pin "17") (pinfunction "B3_17") (pintype "unspecified"))
    )
    (net (code "110") (name "Vlogic-02in{slash}out") (class "Default")
      (node (ref "U10") (pin "32") (pinfunction "IOT_43a_32") (pintype "unspecified"))
      (node (ref "VLOGIC1") (pin "4") (pinfunction "A3_4") (pintype "unspecified"))
    )
    (net (code "111") (name "Vlogic-03") (class "Default")
      (node (ref "RN3") (pin "8") (pinfunction "8_8") (pintype "unspecified"))
      (node (ref "VLOGIC1") (pin "16") (pinfunction "B4_16") (pintype "unspecified"))
    )
    (net (code "112") (name "Vlogic-03in{slash}out") (class "Default")
      (node (ref "U10") (pin "31") (pinfunction "IOT_42b_31") (pintype "unspecified"))
      (node (ref "VLOGIC1") (pin "5") (pinfunction "A4_5") (pintype "unspecified"))
    )
    (net (code "113") (name "Vlogic-04") (class "Default")
      (node (ref "RN1") (pin "5") (pinfunction "5_5") (pintype "unspecified"))
      (node (ref "VLOGIC1") (pin "15") (pinfunction "B5_15") (pintype "unspecified"))
    )
    (net (code "114") (name "Vlogic-04in{slash}out") (class "Default")
      (node (ref "U10") (pin "28") (pinfunction "IOT_41a_28") (pintype "unspecified"))
      (node (ref "VLOGIC1") (pin "6") (pinfunction "A5_6") (pintype "unspecified"))
    )
    (net (code "115") (name "Vlogic-05") (class "Default")
      (node (ref "RN1") (pin "6") (pinfunction "6_6") (pintype "unspecified"))
      (node (ref "VLOGIC1") (pin "14") (pinfunction "B6_14") (pintype "unspecified"))
    )
    (net (code "116") (name "Vlogic-05in{slash}out") (class "Default")
      (node (ref "U10") (pin "27") (pinfunction "IOT_38b_27") (pintype "unspecified"))
      (node (ref "VLOGIC1") (pin "7") (pinfunction "A6_7") (pintype "unspecified"))
    )
    (net (code "117") (name "Vlogic-06") (class "Default")
      (node (ref "RN1") (pin "7") (pinfunction "7_7") (pintype "unspecified"))
      (node (ref "VLOGIC1") (pin "13") (pinfunction "B7_13") (pintype "unspecified"))
    )
    (net (code "118") (name "Vlogic-06in{slash}out") (class "Default")
      (node (ref "U10") (pin "26") (pinfunction "IOT_39a_26") (pintype "unspecified"))
      (node (ref "VLOGIC1") (pin "8") (pinfunction "A7_8") (pintype "unspecified"))
    )
    (net (code "119") (name "Vlogic-07") (class "Default")
      (node (ref "RN1") (pin "8") (pinfunction "8_8") (pintype "unspecified"))
      (node (ref "VLOGIC1") (pin "12") (pinfunction "B8_12") (pintype "unspecified"))
    )
    (net (code "120") (name "Vlogic-07in{slash}out") (class "Default")
      (node (ref "U10") (pin "25") (pinfunction "IOT_36b_25") (pintype "unspecified"))
      (node (ref "VLOGIC1") (pin "9") (pinfunction "A8_9") (pintype "unspecified"))
    )
    (net (code "121") (name "Vlogic_OE") (class "Default")
      (node (ref "R15") (pin "1") (pinfunction "1_1") (pintype "unspecified"))
      (node (ref "U10") (pin "42") (pinfunction "IOT_51a_42") (pintype "unspecified"))
      (node (ref "VLOGIC1") (pin "10") (pinfunction "OE_10") (pintype "unspecified"))
    )
    (net (code "122") (name "Vpp_2v5") (class "Default")
      (node (ref "C22") (pin "1") (pinfunction "1_1") (pintype "input"))
      (node (ref "C23") (pin "2") (pinfunction "2_2") (pintype "input"))
      (node (ref "C24") (pin "2") (pinfunction "2_2") (pintype "input"))
      (node (ref "C25") (pin "2") (pinfunction "2_2") (pintype "input"))
      (node (ref "C26") (pin "2") (pinfunction "2_2") (pintype "input"))
      (node (ref "C27") (pin "2") (pinfunction "2_2") (pintype "input"))
      (node (ref "D2") (pin "1") (pinfunction "C_1") (pintype "unspecified"))
      (node (ref "U10") (pin "24") (pinfunction "VPP_2V5_24") (pintype "unspecified"))
    )
    (net (code "123") (name "unconnected-(U2-VOUT(TAB)-Pad2)") (class "Default")
      (node (ref "U2") (pin "2") (pinfunction "VOUT(TAB)_2") (pintype "unspecified+no_connect"))
    )
    (net (code "124") (name "unconnected-(U3-VOUT(TAB)-Pad2)") (class "Default")
      (node (ref "U3") (pin "2") (pinfunction "VOUT(TAB)_2") (pintype "unspecified+no_connect"))
    )
  )
)
